# octanis_eps_v05.net
KiCad netlist of a schematic drawn in EAGLE
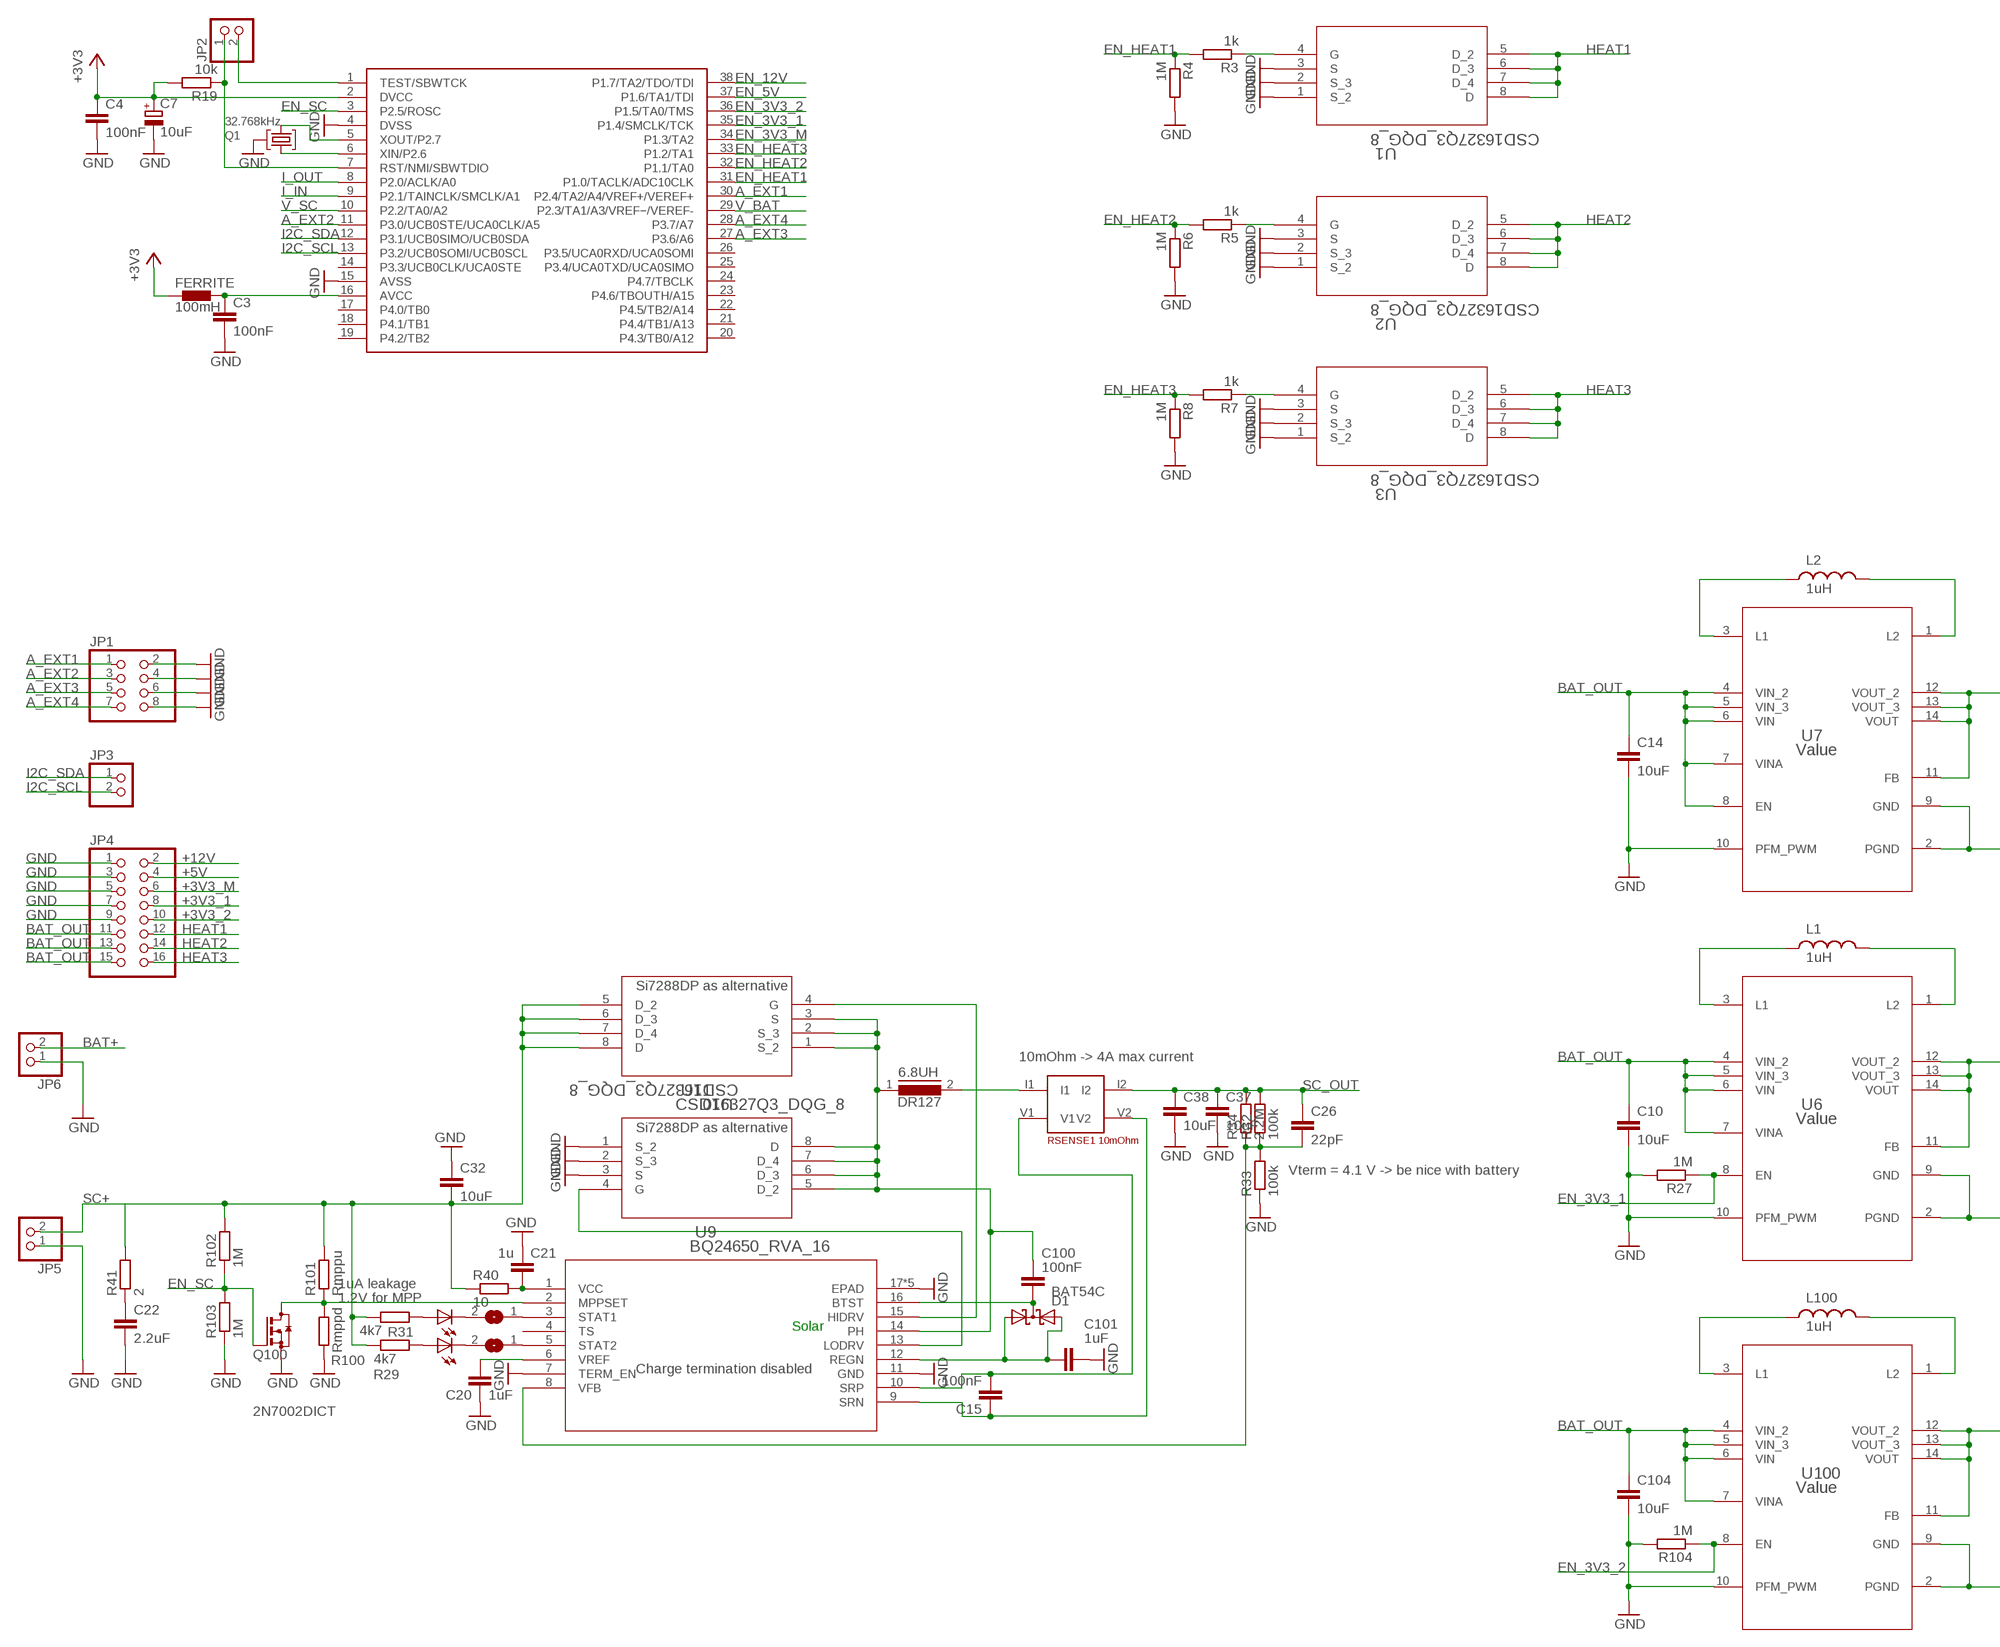
[diagram p0: schematic, sheet 1, part 1 of 2]
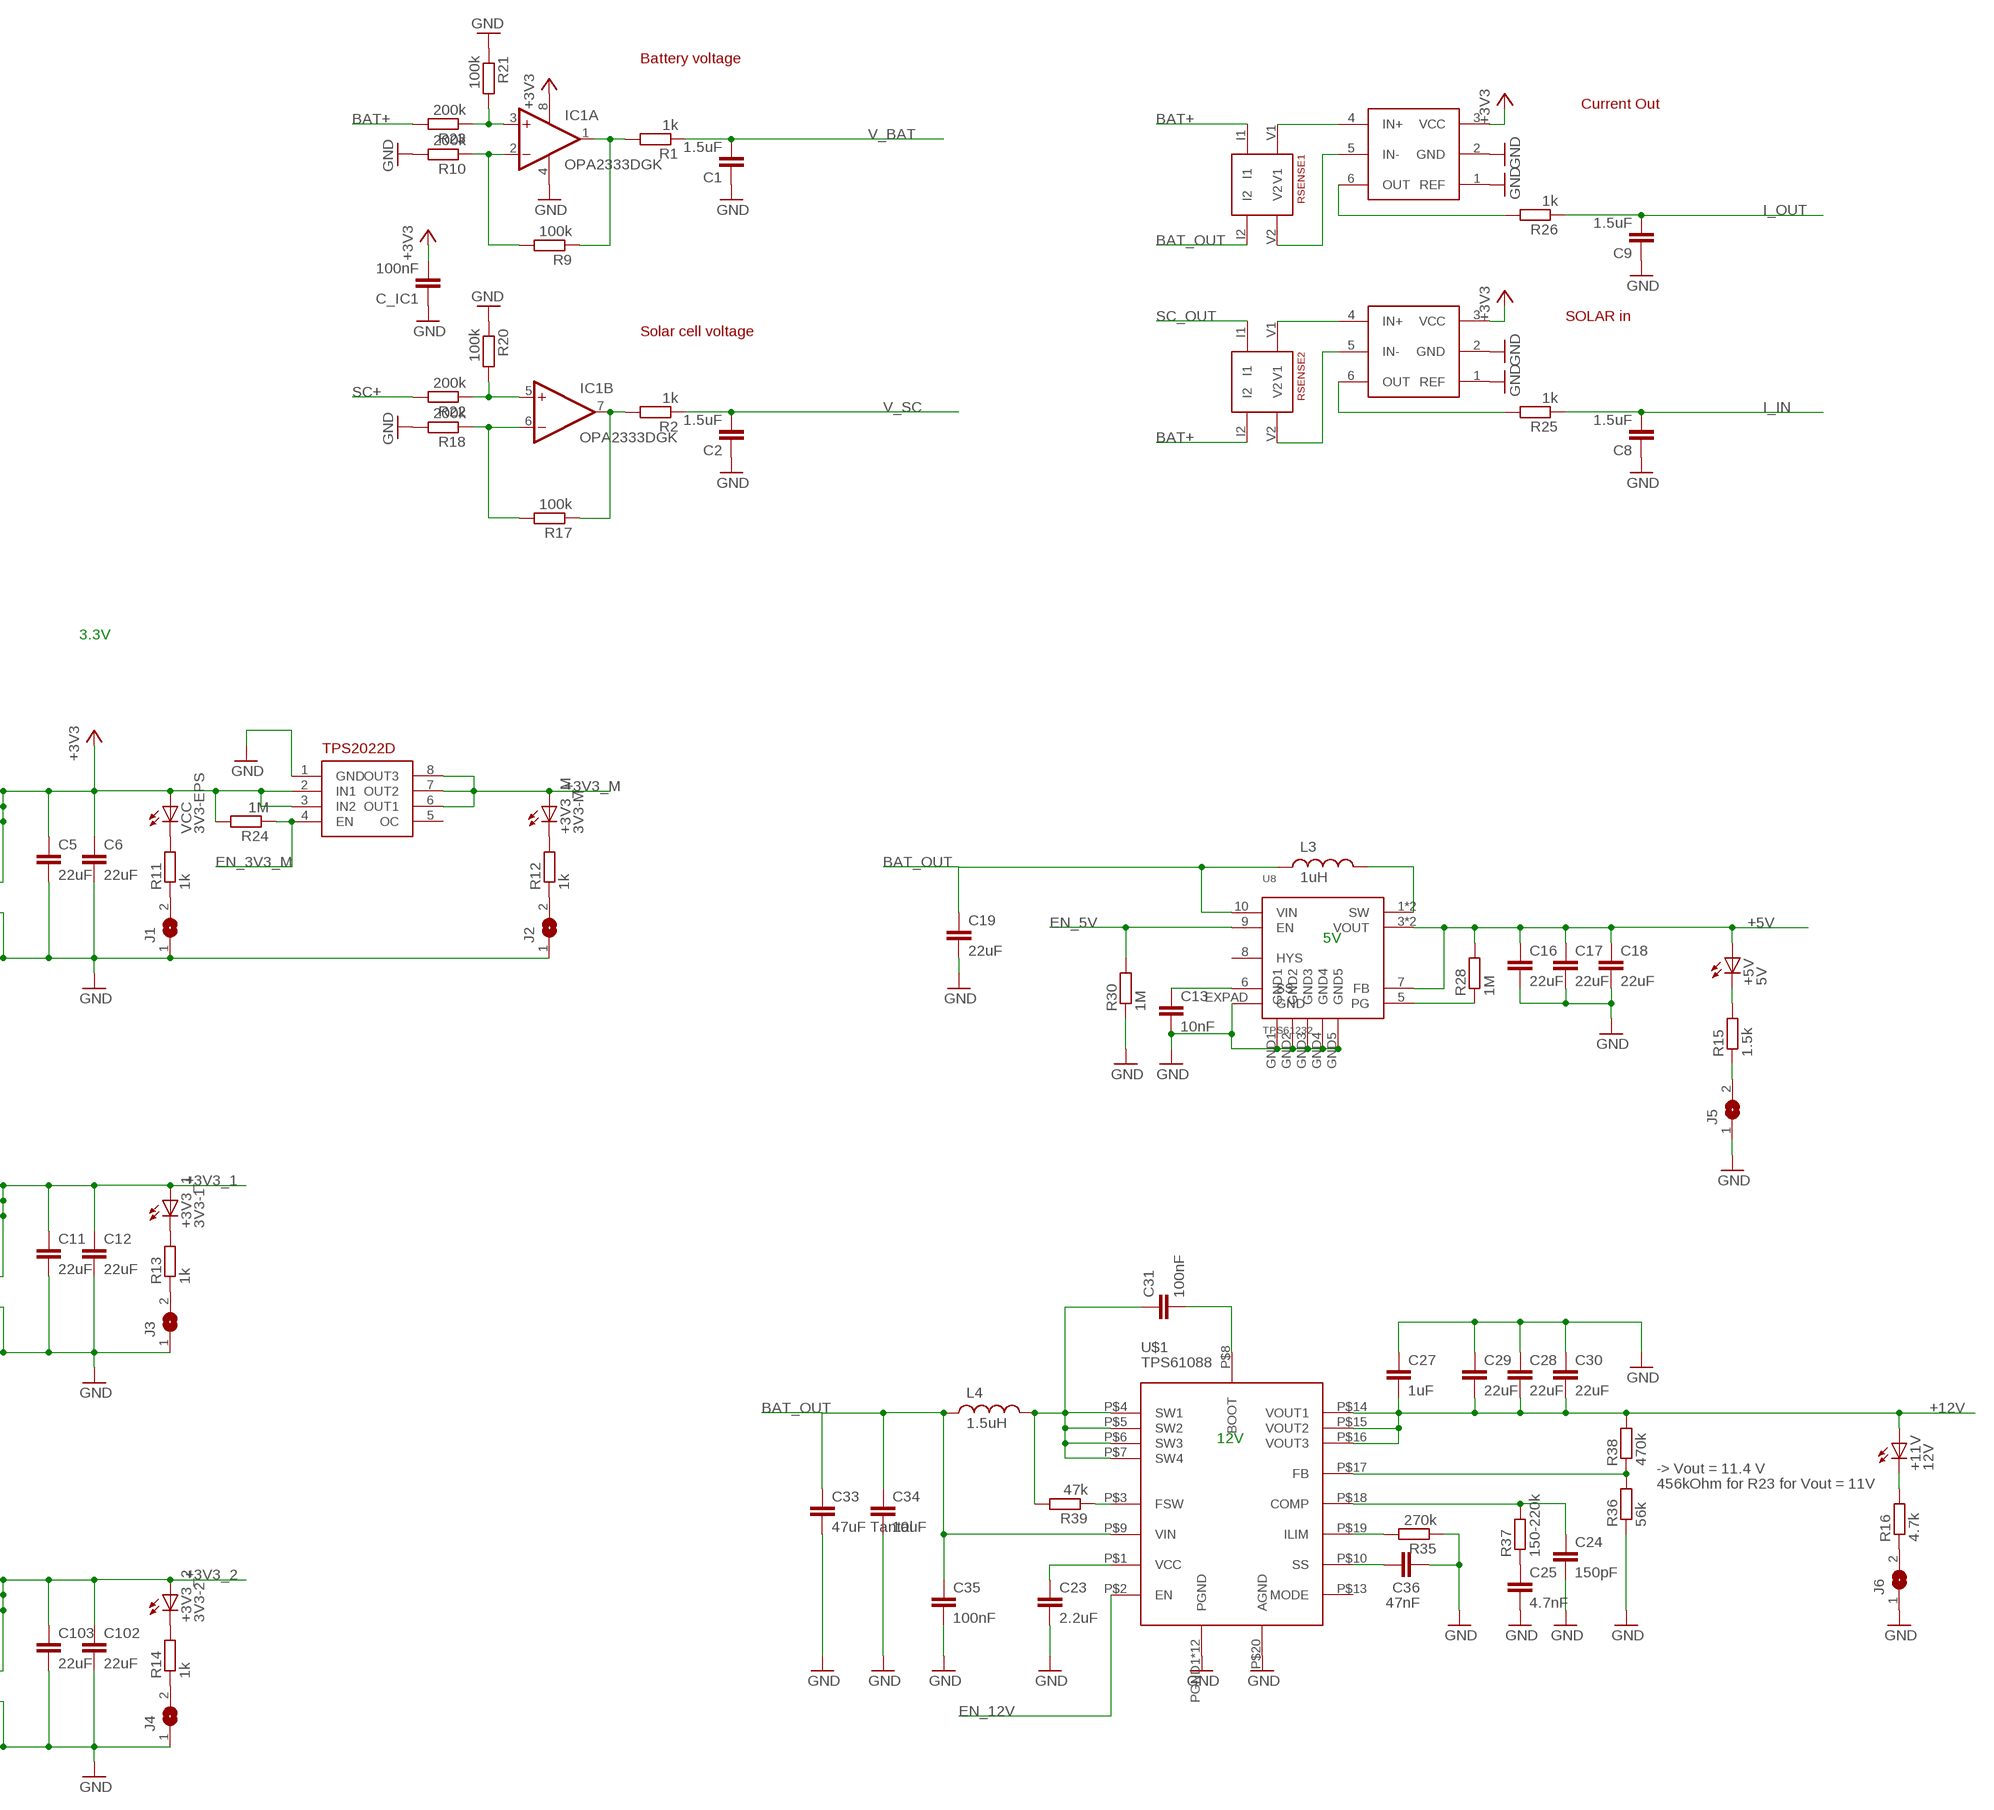
[diagram p1: schematic, sheet 1, part 2 of 2]

(export (version "E")
  (design (tool "Eeschema 10.0.6"))
  (components
    (comp (ref "+3V3_1")
      (value "3V3-1")
      (footprint "eagle-import:CHIPLED_0603")
      (libsource (lib "eagle-import") (part "LEDCHIPLED_0603"))
    )
    (comp (ref "+3V3_2")
      (value "3V3-2")
      (footprint "eagle-import:CHIPLED_0603")
      (libsource (lib "eagle-import") (part "LEDCHIPLED_0603"))
    )
    (comp (ref "+3V3_M")
      (value "3V3-M")
      (footprint "eagle-import:CHIPLED_0603")
      (libsource (lib "eagle-import") (part "LEDCHIPLED_0603"))
    )
    (comp (ref "+5V")
      (value "5V")
      (footprint "eagle-import:CHIPLED_0603")
      (libsource (lib "eagle-import") (part "LEDCHIPLED_0603"))
    )
    (comp (ref "+11V")
      (value "12V")
      (footprint "eagle-import:CHIPLED_0603")
      (libsource (lib "eagle-import") (part "LEDCHIPLED_0603"))
    )
    (comp (ref "6.8UH")
      (value "DR127")
      (footprint "eagle-import:DR127")
      (libsource (lib "eagle-import") (part "DR127"))
    )
    (comp (ref "C1")
      (value "1.5uF")
      (footprint "eagle-import:C0603")
      (libsource (lib "eagle-import") (part "C-EUC0603"))
    )
    (comp (ref "C2")
      (value "1.5uF")
      (footprint "eagle-import:C0603")
      (libsource (lib "eagle-import") (part "C-EUC0603"))
    )
    (comp (ref "C3")
      (value "100nF")
      (footprint "eagle-import:C0603")
      (libsource (lib "eagle-import") (part "C-EUC0603"))
    )
    (comp (ref "C4")
      (value "100nF")
      (footprint "eagle-import:C0603")
      (libsource (lib "eagle-import") (part "C-EUC0603"))
    )
    (comp (ref "C5")
      (value "22uF")
      (footprint "eagle-import:C0805")
      (libsource (lib "eagle-import") (part "resistor_C-EUC0805"))
    )
    (comp (ref "C6")
      (value "22uF")
      (footprint "eagle-import:C0805")
      (libsource (lib "eagle-import") (part "resistor_C-EUC0805"))
    )
    (comp (ref "C7")
      (value "10uF")
      (footprint "eagle-import:A_3216-18R")
      (libsource (lib "eagle-import") (part "CPOL-EUA/3216-18R"))
    )
    (comp (ref "C8")
      (value "1.5uF")
      (footprint "eagle-import:C0603")
      (libsource (lib "eagle-import") (part "C-EUC0603"))
    )
    (comp (ref "C9")
      (value "1.5uF")
      (footprint "eagle-import:C0603")
      (libsource (lib "eagle-import") (part "C-EUC0603"))
    )
    (comp (ref "C10")
      (value "10uF")
      (footprint "eagle-import:C0805")
      (libsource (lib "eagle-import") (part "resistor_C-EUC0805"))
    )
    (comp (ref "C11")
      (value "22uF")
      (footprint "eagle-import:C0805")
      (libsource (lib "eagle-import") (part "resistor_C-EUC0805"))
    )
    (comp (ref "C12")
      (value "22uF")
      (footprint "eagle-import:C0805")
      (libsource (lib "eagle-import") (part "resistor_C-EUC0805"))
    )
    (comp (ref "C13")
      (value "10nF")
      (footprint "eagle-import:C0603")
      (libsource (lib "eagle-import") (part "C-EUC0603"))
    )
    (comp (ref "C14")
      (value "10uF")
      (footprint "eagle-import:C0805")
      (libsource (lib "eagle-import") (part "resistor_C-EUC0805"))
    )
    (comp (ref "C15")
      (value "100nF")
      (footprint "eagle-import:C0603")
      (libsource (lib "eagle-import") (part "C-EUC0603"))
    )
    (comp (ref "C16")
      (value "22uF")
      (footprint "eagle-import:C0805")
      (libsource (lib "eagle-import") (part "resistor_C-EUC0805"))
    )
    (comp (ref "C17")
      (value "22uF")
      (footprint "eagle-import:C0805")
      (libsource (lib "eagle-import") (part "resistor_C-EUC0805"))
    )
    (comp (ref "C18")
      (value "22uF")
      (footprint "eagle-import:C0805")
      (libsource (lib "eagle-import") (part "resistor_C-EUC0805"))
    )
    (comp (ref "C19")
      (value "22uF")
      (footprint "eagle-import:C0603")
      (libsource (lib "eagle-import") (part "C-EUC0603"))
    )
    (comp (ref "C20")
      (value "1uF")
      (footprint "eagle-import:C0603")
      (libsource (lib "eagle-import") (part "C-EUC0603"))
    )
    (comp (ref "C21")
      (value "1u")
      (footprint "eagle-import:C0603")
      (libsource (lib "eagle-import") (part "C-EUC0603"))
    )
    (comp (ref "C22")
      (value "2.2uF")
      (footprint "eagle-import:C0603")
      (libsource (lib "eagle-import") (part "C-EUC0603"))
    )
    (comp (ref "C23")
      (value "2.2uF")
      (footprint "eagle-import:C0603")
      (libsource (lib "eagle-import") (part "C-EUC0603"))
    )
    (comp (ref "C24")
      (value "150pF")
      (footprint "eagle-import:C0603")
      (libsource (lib "eagle-import") (part "C-EUC0603"))
    )
    (comp (ref "C25")
      (value "4.7nF")
      (footprint "eagle-import:C0603")
      (libsource (lib "eagle-import") (part "C-EUC0603"))
    )
    (comp (ref "C26")
      (value "22pF")
      (footprint "eagle-import:C0603")
      (libsource (lib "eagle-import") (part "C-EUC0603"))
    )
    (comp (ref "C27")
      (value "1uF")
      (footprint "eagle-import:C0603")
      (libsource (lib "eagle-import") (part "C-EUC0603"))
    )
    (comp (ref "C28")
      (value "22uF")
      (footprint "eagle-import:C0805")
      (libsource (lib "eagle-import") (part "resistor_C-EUC0805"))
    )
    (comp (ref "C29")
      (value "22uF")
      (footprint "eagle-import:C0805")
      (libsource (lib "eagle-import") (part "resistor_C-EUC0805"))
    )
    (comp (ref "C30")
      (value "22uF")
      (footprint "eagle-import:C0805")
      (libsource (lib "eagle-import") (part "resistor_C-EUC0805"))
    )
    (comp (ref "C31")
      (value "100nF")
      (footprint "eagle-import:C0603")
      (libsource (lib "eagle-import") (part "C-EUC0603"))
    )
    (comp (ref "C32")
      (value "10uF")
      (footprint "eagle-import:C0805")
      (libsource (lib "eagle-import") (part "resistor_C-EUC0805"))
    )
    (comp (ref "C33")
      (value "47uF Tantal")
      (footprint "eagle-import:C1210")
      (libsource (lib "eagle-import") (part "C-EUC1210"))
    )
    (comp (ref "C34")
      (value "10uF")
      (footprint "eagle-import:C0805")
      (libsource (lib "eagle-import") (part "resistor_C-EUC0805"))
    )
    (comp (ref "C35")
      (value "100nF")
      (footprint "eagle-import:C0603")
      (libsource (lib "eagle-import") (part "C-EUC0603"))
    )
    (comp (ref "C36")
      (value "47nF")
      (footprint "eagle-import:C0603")
      (libsource (lib "eagle-import") (part "C-EUC0603"))
    )
    (comp (ref "C37")
      (value "10uF")
      (footprint "eagle-import:C0805")
      (libsource (lib "eagle-import") (part "resistor_C-EUC0805"))
    )
    (comp (ref "C38")
      (value "10uF")
      (footprint "eagle-import:C0805")
      (libsource (lib "eagle-import") (part "resistor_C-EUC0805"))
    )
    (comp (ref "C100")
      (value "100nF")
      (footprint "eagle-import:C0603")
      (libsource (lib "eagle-import") (part "C-EUC0603"))
    )
    (comp (ref "C101")
      (value "1uF")
      (footprint "eagle-import:C0603")
      (libsource (lib "eagle-import") (part "C-EUC0603"))
    )
    (comp (ref "C102")
      (value "22uF")
      (footprint "eagle-import:C0805")
      (libsource (lib "eagle-import") (part "resistor_C-EUC0805"))
    )
    (comp (ref "C103")
      (value "22uF")
      (footprint "eagle-import:C0805")
      (libsource (lib "eagle-import") (part "resistor_C-EUC0805"))
    )
    (comp (ref "C104")
      (value "10uF")
      (footprint "eagle-import:C0805")
      (libsource (lib "eagle-import") (part "resistor_C-EUC0805"))
    )
    (comp (ref "C_IC1")
      (value "100nF")
      (footprint "eagle-import:C0603")
      (libsource (lib "eagle-import") (part "C-EUC0603"))
    )
    (comp (ref "D1")
      (value "BAT54C")
      (footprint "eagle-import:SOT23")
      (libsource (lib "eagle-import") (part "BAT54C"))
    )
    (comp (ref "FERRITE")
      (value "100mH")
      (footprint "eagle-import:0402")
      (libsource (lib "eagle-import") (part "BLM15HD601SN1"))
    )
    (comp (ref "IC1")
      (value "OPA2333DGK")
      (footprint "eagle-import:MSOP08")
      (libsource (lib "eagle-import") (part "OPA2333DGK"))
    )
    (comp (ref "J1") (value "SJ") (footprint "eagle-import:SJ") (libsource (lib "eagle-import") (part "SJ")))
    (comp (ref "J2") (value "SJ") (footprint "eagle-import:SJ") (libsource (lib "eagle-import") (part "SJ")))
    (comp (ref "J3") (value "SJ") (footprint "eagle-import:SJ") (libsource (lib "eagle-import") (part "SJ")))
    (comp (ref "J4") (value "SJ") (footprint "eagle-import:SJ") (libsource (lib "eagle-import") (part "SJ")))
    (comp (ref "J5") (value "SJ") (footprint "eagle-import:SJ") (libsource (lib "eagle-import") (part "SJ")))
    (comp (ref "J6") (value "SJ") (footprint "eagle-import:SJ") (libsource (lib "eagle-import") (part "SJ")))
    (comp (ref "J7") (value "SJ") (footprint "eagle-import:SJ") (libsource (lib "eagle-import") (part "SJ")))
    (comp (ref "J8") (value "SJ") (footprint "eagle-import:SJ") (libsource (lib "eagle-import") (part "SJ")))
    (comp (ref "JP1")
      (value "PINHD-2X4")
      (footprint "eagle-import:2X04")
      (libsource (lib "eagle-import") (part "PINHD-2X4"))
    )
    (comp (ref "JP2")
      (value "PINHD-1X2")
      (footprint "eagle-import:1X02")
      (libsource (lib "eagle-import") (part "PINHD-1X2"))
    )
    (comp (ref "JP3")
      (value "PINHD-1X2")
      (footprint "eagle-import:1X02")
      (libsource (lib "eagle-import") (part "PINHD-1X2"))
    )
    (comp (ref "JP4")
      (value "PINHD-2X8")
      (footprint "eagle-import:2X08")
      (libsource (lib "eagle-import") (part "PINHD-2X8"))
    )
    (comp (ref "JP5")
      (value "PINHD-1X2")
      (footprint "eagle-import:1X02")
      (libsource (lib "eagle-import") (part "PINHD-1X2"))
    )
    (comp (ref "JP6")
      (value "PINHD-1X2")
      (footprint "eagle-import:1X02")
      (libsource (lib "eagle-import") (part "PINHD-1X2"))
    )
    (comp (ref "L1")
      (value "1uH")
      (footprint "eagle-import:XFL4020")
      (libsource (lib "eagle-import") (part "XFL4020"))
    )
    (comp (ref "L2")
      (value "1uH")
      (footprint "eagle-import:XFL4020")
      (libsource (lib "eagle-import") (part "XFL4020"))
    )
    (comp (ref "L3")
      (value "1uH")
      (footprint "eagle-import:XFL4020")
      (libsource (lib "eagle-import") (part "XFL4020"))
    )
    (comp (ref "L4")
      (value "1.5uH")
      (footprint "eagle-import:XFL4020")
      (libsource (lib "eagle-import") (part "XFL4020"))
    )
    (comp (ref "L100")
      (value "1uH")
      (footprint "eagle-import:XFL4020")
      (libsource (lib "eagle-import") (part "XFL4020"))
    )
    (comp (ref "Q1")
      (value "32.768kHz")
      (footprint "eagle-import:MS3V-T1R")
      (libsource (lib "eagle-import") (part "MS3V-T1R"))
    )
    (comp (ref "Q100")
      (value "BSS123")
      (footprint "eagle-import:SOT23")
      (libsource (lib "eagle-import") (part "BSS123"))
    )
    (comp (ref "R1")
      (value "1k")
      (footprint "eagle-import:R0603")
      (libsource (lib "eagle-import") (part "R-EU_R0603"))
    )
    (comp (ref "R2")
      (value "1k")
      (footprint "eagle-import:R0603")
      (libsource (lib "eagle-import") (part "R-EU_R0603"))
    )
    (comp (ref "R3")
      (value "1k")
      (footprint "eagle-import:R0603")
      (libsource (lib "eagle-import") (part "R-EU_R0603"))
    )
    (comp (ref "R4")
      (value "1M")
      (footprint "eagle-import:R0603")
      (libsource (lib "eagle-import") (part "R-EU_R0603"))
    )
    (comp (ref "R5")
      (value "1k")
      (footprint "eagle-import:R0603")
      (libsource (lib "eagle-import") (part "R-EU_R0603"))
    )
    (comp (ref "R6")
      (value "1M")
      (footprint "eagle-import:R0603")
      (libsource (lib "eagle-import") (part "R-EU_R0603"))
    )
    (comp (ref "R7")
      (value "1k")
      (footprint "eagle-import:R0603")
      (libsource (lib "eagle-import") (part "R-EU_R0603"))
    )
    (comp (ref "R8")
      (value "1M")
      (footprint "eagle-import:R0603")
      (libsource (lib "eagle-import") (part "R-EU_R0603"))
    )
    (comp (ref "R9")
      (value "100k")
      (footprint "eagle-import:R0603")
      (libsource (lib "eagle-import") (part "R-EU_R0603"))
    )
    (comp (ref "R10")
      (value "200k")
      (footprint "eagle-import:R0603")
      (libsource (lib "eagle-import") (part "R-EU_R0603"))
    )
    (comp (ref "R11")
      (value "1k")
      (footprint "eagle-import:R0603")
      (libsource (lib "eagle-import") (part "R-EU_R0603"))
    )
    (comp (ref "R12")
      (value "1k")
      (footprint "eagle-import:R0603")
      (libsource (lib "eagle-import") (part "R-EU_R0603"))
    )
    (comp (ref "R13")
      (value "1k")
      (footprint "eagle-import:R0603")
      (libsource (lib "eagle-import") (part "R-EU_R0603"))
    )
    (comp (ref "R14")
      (value "1k")
      (footprint "eagle-import:R0603")
      (libsource (lib "eagle-import") (part "R-EU_R0603"))
    )
    (comp (ref "R15")
      (value "1.5k")
      (footprint "eagle-import:R0603")
      (libsource (lib "eagle-import") (part "R-EU_R0603"))
    )
    (comp (ref "R16")
      (value "4.7k")
      (footprint "eagle-import:R0603")
      (libsource (lib "eagle-import") (part "R-EU_R0603"))
    )
    (comp (ref "R17")
      (value "100k")
      (footprint "eagle-import:R0603")
      (libsource (lib "eagle-import") (part "R-EU_R0603"))
    )
    (comp (ref "R18")
      (value "200k")
      (footprint "eagle-import:R0603")
      (libsource (lib "eagle-import") (part "R-EU_R0603"))
    )
    (comp (ref "R19")
      (value "10k")
      (footprint "eagle-import:R0603")
      (libsource (lib "eagle-import") (part "R-EU_R0603"))
    )
    (comp (ref "R20")
      (value "100k")
      (footprint "eagle-import:R0603")
      (libsource (lib "eagle-import") (part "R-EU_R0603"))
    )
    (comp (ref "R21")
      (value "100k")
      (footprint "eagle-import:R0603")
      (libsource (lib "eagle-import") (part "R-EU_R0603"))
    )
    (comp (ref "R22")
      (value "200k")
      (footprint "eagle-import:R0603")
      (libsource (lib "eagle-import") (part "R-EU_R0603"))
    )
    (comp (ref "R23")
      (value "200k")
      (footprint "eagle-import:R0603")
      (libsource (lib "eagle-import") (part "R-EU_R0603"))
    )
    (comp (ref "R24")
      (value "1M")
      (footprint "eagle-import:R0603")
      (libsource (lib "eagle-import") (part "resistor_R-EU_R0603"))
    )
    (comp (ref "R25")
      (value "1k")
      (footprint "eagle-import:R0603")
      (libsource (lib "eagle-import") (part "R-EU_R0603"))
    )
    (comp (ref "R26")
      (value "1k")
      (footprint "eagle-import:R0603")
      (libsource (lib "eagle-import") (part "R-EU_R0603"))
    )
    (comp (ref "R27")
      (value "1M")
      (footprint "eagle-import:R0603")
      (libsource (lib "eagle-import") (part "resistor_R-EU_R0603"))
    )
    (comp (ref "R28")
      (value "1M")
      (footprint "eagle-import:R0603")
      (libsource (lib "eagle-import") (part "R-EU_R0603"))
    )
    (comp (ref "R29")
      (value "4k7")
      (footprint "eagle-import:R0603")
      (libsource (lib "eagle-import") (part "R-EU_R0603"))
    )
    (comp (ref "R30")
      (value "1M")
      (footprint "eagle-import:R0603")
      (libsource (lib "eagle-import") (part "R-EU_R0603"))
    )
    (comp (ref "R31")
      (value "4k7")
      (footprint "eagle-import:R0603")
      (libsource (lib "eagle-import") (part "R-EU_R0603"))
    )
    (comp (ref "R32")
      (value "100k")
      (footprint "eagle-import:R0603")
      (libsource (lib "eagle-import") (part "R-EU_R0603"))
    )
    (comp (ref "R33")
      (value "100k")
      (footprint "eagle-import:R0603")
      (libsource (lib "eagle-import") (part "R-EU_R0603"))
    )
    (comp (ref "R34")
      (value "2.2M")
      (footprint "eagle-import:R0603")
      (libsource (lib "eagle-import") (part "R-EU_R0603"))
    )
    (comp (ref "R35")
      (value "270k")
      (footprint "eagle-import:R0603")
      (libsource (lib "eagle-import") (part "resistor_R-EU_R0603"))
    )
    (comp (ref "R36")
      (value "56k")
      (footprint "eagle-import:R0603")
      (libsource (lib "eagle-import") (part "resistor_R-EU_R0603"))
    )
    (comp (ref "R37")
      (value "150-220k")
      (footprint "eagle-import:R0603")
      (libsource (lib "eagle-import") (part "resistor_R-EU_R0603"))
    )
    (comp (ref "R38")
      (value "470k")
      (footprint "eagle-import:R0603")
      (libsource (lib "eagle-import") (part "resistor_R-EU_R0603"))
    )
    (comp (ref "R39")
      (value "47k")
      (footprint "eagle-import:R0603")
      (libsource (lib "eagle-import") (part "resistor_R-EU_R0603"))
    )
    (comp (ref "R40")
      (value "10")
      (footprint "eagle-import:R1206")
      (libsource (lib "eagle-import") (part "R-EU_R1206"))
    )
    (comp (ref "R41")
      (value "2")
      (footprint "eagle-import:R2012")
      (libsource (lib "eagle-import") (part "R-EU_R2012"))
    )
    (comp (ref "R100")
      (value "Rmppd")
      (footprint "eagle-import:R0603")
      (libsource (lib "eagle-import") (part "R-EU_R0603"))
    )
    (comp (ref "R101")
      (value "Rmppu")
      (footprint "eagle-import:R0603")
      (libsource (lib "eagle-import") (part "R-EU_R0603"))
    )
    (comp (ref "R102")
      (value "1M")
      (footprint "eagle-import:R0603")
      (libsource (lib "eagle-import") (part "R-EU_R0603"))
    )
    (comp (ref "R103")
      (value "1M")
      (footprint "eagle-import:R0603")
      (libsource (lib "eagle-import") (part "R-EU_R0603"))
    )
    (comp (ref "R104")
      (value "1M")
      (footprint "eagle-import:R0603")
      (libsource (lib "eagle-import") (part "resistor_R-EU_R0603"))
    )
    (comp (ref "RSENSE1")
      (value "RSENSE2")
      (footprint "eagle-import:4PADS_RESISTOR")
      (libsource (lib "eagle-import") (part "CURRENT_RESISTOR"))
    )
    (comp (ref "R_SENSE1")
      (value "RSENSE1 10mOhm")
      (footprint "eagle-import:4PADS_RESISTOR")
      (libsource (lib "eagle-import") (part "CURRENT_RESISTOR"))
    )
    (comp (ref "R_SENSE2")
      (value "RSENSE1")
      (footprint "eagle-import:4PADS_RESISTOR")
      (libsource (lib "eagle-import") (part "CURRENT_RESISTOR"))
    )
    (comp (ref "STAT1")
      (value "5V-ok")
      (footprint "eagle-import:CHIPLED_0603")
      (libsource (lib "eagle-import") (part "LEDCHIPLED_0603"))
    )
    (comp (ref "STAT2")
      (value "5V-ok")
      (footprint "eagle-import:CHIPLED_0603")
      (libsource (lib "eagle-import") (part "LEDCHIPLED_0603"))
    )
    (comp (ref "U$1")
      (value "TPS61088")
      (footprint "eagle-import:R-PVQFN-N20")
      (libsource (lib "eagle-import") (part "TPS61088"))
    )
    (comp (ref "U$2")
      (value "INA213")
      (footprint "eagle-import:SC70-6")
      (libsource (lib "eagle-import") (part "INA213"))
    )
    (comp (ref "U$3")
      (value "INA213")
      (footprint "eagle-import:SC70-6")
      (libsource (lib "eagle-import") (part "INA213"))
    )
    (comp (ref "U1")
      (value "CSD16327Q3_DQG_8")
      (footprint "eagle-import:DQG8")
      (fields
        (field (name "GENERIC_PART_NUMBER") "CSD16327Q3")
        (field (name "MANUFACTURER") "Texas Instruments")
      )
      (libsource (lib "eagle-import") (part "CSD16327Q3_DQG_8"))
    )
    (comp (ref "U2")
      (value "CSD16327Q3_DQG_8")
      (footprint "eagle-import:DQG8")
      (fields
        (field (name "GENERIC_PART_NUMBER") "CSD16327Q3")
        (field (name "MANUFACTURER") "Texas Instruments")
      )
      (libsource (lib "eagle-import") (part "CSD16327Q3_DQG_8"))
    )
    (comp (ref "U3")
      (value "CSD16327Q3_DQG_8")
      (footprint "eagle-import:DQG8")
      (fields
        (field (name "GENERIC_PART_NUMBER") "CSD16327Q3")
        (field (name "MANUFACTURER") "Texas Instruments")
      )
      (libsource (lib "eagle-import") (part "CSD16327Q3_DQG_8"))
    )
    (comp (ref "U4")
      (value "MSP430G2544")
      (footprint "eagle-import:TSSOP38")
      (libsource (lib "eagle-import") (part "MSP430G2544"))
    )
    (comp (ref "U5")
      (value "TPS2022D")
      (footprint "eagle-import:SO8")
      (libsource (lib "eagle-import") (part "TPS2022D"))
    )
    (comp (ref "U6")
      (value "Value")
      (footprint "eagle-import:RNC0014A")
      (fields
        (field (name "ALTERNATEPARTNUMBER") "TPS630250RNCT")
        (field (name "MANUFACTURER") "Texas Instruments")
        (field (name "PARTNUMBER") "TPS630250RNCR")
      )
      (libsource (lib "eagle-import") (part "TPS630250RNCR"))
    )
    (comp (ref "U7")
      (value "Value")
      (footprint "eagle-import:RNC0014A")
      (fields
        (field (name "ALTERNATEPARTNUMBER") "TPS630250RNCT")
        (field (name "MANUFACTURER") "Texas Instruments")
        (field (name "PARTNUMBER") "TPS630250RNCR")
      )
      (libsource (lib "eagle-import") (part "TPS630250RNCR"))
    )
    (comp (ref "U8")
      (value "TPS61232")
      (footprint "eagle-import:S-PVSON-N10")
      (libsource (lib "eagle-import") (part "TPS61232"))
    )
    (comp (ref "U9")
      (value "BQ24650_RVA_16")
      (footprint "eagle-import:RVA16_2P14X2P14")
      (fields
        (field (name "GENERIC_PART_NUMBER") "BQ24650")
        (field (name "MANUFACTURER") "Texas Instruments")
      )
      (libsource (lib "eagle-import") (part "BQ24650_RVA_16"))
    )
    (comp (ref "U10")
      (value "CSD16327Q3_DQG_8")
      (footprint "eagle-import:DQG8")
      (fields
        (field (name "GENERIC_PART_NUMBER") "CSD16327Q3")
        (field (name "MANUFACTURER") "Texas Instruments")
      )
      (libsource (lib "eagle-import") (part "CSD16327Q3_DQG_8"))
    )
    (comp (ref "U11")
      (value "CSD16327Q3_DQG_8")
      (footprint "eagle-import:DQG8")
      (fields
        (field (name "GENERIC_PART_NUMBER") "CSD16327Q3")
        (field (name "MANUFACTURER") "Texas Instruments")
      )
      (libsource (lib "eagle-import") (part "CSD16327Q3_DQG_8"))
    )
    (comp (ref "U100")
      (value "Value")
      (footprint "eagle-import:RNC0014A")
      (fields
        (field (name "ALTERNATEPARTNUMBER") "TPS630250RNCT")
        (field (name "MANUFACTURER") "Texas Instruments")
        (field (name "PARTNUMBER") "TPS630250RNCR")
      )
      (libsource (lib "eagle-import") (part "TPS630250RNCR"))
    )
    (comp (ref "VCC")
      (value "3V3-EPS")
      (footprint "eagle-import:CHIPLED_0603")
      (libsource (lib "eagle-import") (part "LEDCHIPLED_0603"))
    )
  )
  (nets
    (net (code "1") (name "+3V3") (class "Default")
      (node (ref "C4") (pin "1") (pinfunction "1_1") (pintype "passive"))
      (node (ref "C5") (pin "1") (pinfunction "1_1") (pintype "passive"))
      (node (ref "C6") (pin "1") (pinfunction "1_1") (pintype "passive"))
      (node (ref "C7") (pin "+") (pinfunction "+_+") (pintype "passive"))
      (node (ref "C_IC1") (pin "2") (pinfunction "2_2") (pintype "passive"))
      (node (ref "FERRITE") (pin "1") (pinfunction "1_1") (pintype "passive"))
      (node (ref "IC1") (pin "8") (pinfunction "V+_8") (pintype "power_in"))
      (node (ref "R19") (pin "2") (pinfunction "2_2") (pintype "passive"))
      (node (ref "R24") (pin "2") (pinfunction "2_2") (pintype "passive"))
      (node (ref "U$2") (pin "3") (pinfunction "VCC_3") (pintype "bidirectional"))
      (node (ref "U$3") (pin "3") (pinfunction "VCC_3") (pintype "bidirectional"))
      (node (ref "U4") (pin "2") (pinfunction "DVCC_2") (pintype "bidirectional"))
      (node (ref "U5") (pin "2") (pinfunction "IN1_2") (pintype "bidirectional"))
      (node (ref "U5") (pin "3") (pinfunction "IN2_3") (pintype "bidirectional"))
      (node (ref "U7") (pin "11") (pinfunction "FB_11") (pintype "input"))
      (node (ref "U7") (pin "12") (pinfunction "VOUT_2_12") (pintype "power_in"))
      (node (ref "U7") (pin "13") (pinfunction "VOUT_3_13") (pintype "power_in"))
      (node (ref "U7") (pin "14") (pinfunction "VOUT_14") (pintype "power_in"))
      (node (ref "VCC") (pin "A") (pinfunction "A_A") (pintype "passive"))
    )
    (net (code "2") (name "/+3V3_1") (class "Default")
      (node (ref "+3V3_1") (pin "A") (pinfunction "A_A") (pintype "passive"))
      (node (ref "C11") (pin "1") (pinfunction "1_1") (pintype "passive"))
      (node (ref "C12") (pin "1") (pinfunction "1_1") (pintype "passive"))
      (node (ref "JP4") (pin "8") (pinfunction "8_8") (pintype "passive"))
      (node (ref "U6") (pin "11") (pinfunction "FB_11") (pintype "input"))
      (node (ref "U6") (pin "12") (pinfunction "VOUT_2_12") (pintype "power_in"))
      (node (ref "U6") (pin "13") (pinfunction "VOUT_3_13") (pintype "power_in"))
      (node (ref "U6") (pin "14") (pinfunction "VOUT_14") (pintype "power_in"))
    )
    (net (code "3") (name "/+3V3_2") (class "Default")
      (node (ref "+3V3_2") (pin "A") (pinfunction "A_A") (pintype "passive"))
      (node (ref "C102") (pin "1") (pinfunction "1_1") (pintype "passive"))
      (node (ref "C103") (pin "1") (pinfunction "1_1") (pintype "passive"))
      (node (ref "JP4") (pin "10") (pinfunction "10_10") (pintype "passive"))
      (node (ref "U100") (pin "11") (pinfunction "FB_11") (pintype "input"))
      (node (ref "U100") (pin "12") (pinfunction "VOUT_2_12") (pintype "power_in"))
      (node (ref "U100") (pin "13") (pinfunction "VOUT_3_13") (pintype "power_in"))
      (node (ref "U100") (pin "14") (pinfunction "VOUT_14") (pintype "power_in"))
    )
    (net (code "4") (name "/+3V3_M") (class "Default")
      (node (ref "+3V3_M") (pin "A") (pinfunction "A_A") (pintype "passive"))
      (node (ref "JP4") (pin "6") (pinfunction "6_6") (pintype "passive"))
      (node (ref "U5") (pin "6") (pinfunction "OUT1_6") (pintype "bidirectional"))
      (node (ref "U5") (pin "7") (pinfunction "OUT2_7") (pintype "bidirectional"))
      (node (ref "U5") (pin "8") (pinfunction "OUT3_8") (pintype "bidirectional"))
    )
    (net (code "5") (name "/+5V") (class "Default")
      (node (ref "+5V") (pin "A") (pinfunction "A_A") (pintype "passive"))
      (node (ref "C16") (pin "1") (pinfunction "1_1") (pintype "passive"))
      (node (ref "C17") (pin "1") (pinfunction "1_1") (pintype "passive"))
      (node (ref "C18") (pin "1") (pinfunction "1_1") (pintype "passive"))
      (node (ref "JP4") (pin "4") (pinfunction "4_4") (pintype "passive"))
      (node (ref "R28") (pin "2") (pinfunction "2_2") (pintype "passive"))
      (node (ref "U8") (pin "3") (pinfunction "VOUT_3") (pintype "power_in"))
      (node (ref "U8") (pin "4") (pinfunction "VOUT_4") (pintype "power_in"))
      (node (ref "U8") (pin "7") (pinfunction "FB_7") (pintype "input"))
    )
    (net (code "6") (name "/+12V") (class "Default")
      (node (ref "+11V") (pin "A") (pinfunction "A_A") (pintype "passive"))
      (node (ref "C27") (pin "2") (pinfunction "2_2") (pintype "passive"))
      (node (ref "C28") (pin "2") (pinfunction "2_2") (pintype "passive"))
      (node (ref "C29") (pin "2") (pinfunction "2_2") (pintype "passive"))
      (node (ref "C30") (pin "2") (pinfunction "2_2") (pintype "passive"))
      (node (ref "JP4") (pin "2") (pinfunction "2_2") (pintype "passive"))
      (node (ref "R38") (pin "2") (pinfunction "2_2") (pintype "passive"))
      (node (ref "U$1") (pin "P$14") (pinfunction "VOUT1_P$14") (pintype "bidirectional"))
      (node (ref "U$1") (pin "P$15") (pinfunction "VOUT2_P$15") (pintype "bidirectional"))
      (node (ref "U$1") (pin "P$16") (pinfunction "VOUT3_P$16") (pintype "bidirectional"))
    )
    (net (code "7") (name "/A_EXT1") (class "Default")
      (node (ref "JP1") (pin "1") (pinfunction "1_1") (pintype "passive"))
      (node (ref "U4") (pin "30") (pinfunction "P2.4/TA2/A4/VREF+/VEREF+_30") (pintype "bidirectional"))
    )
    (net (code "8") (name "/A_EXT2") (class "Default")
      (node (ref "JP1") (pin "3") (pinfunction "3_3") (pintype "passive"))
      (node (ref "U4") (pin "11") (pinfunction "P3.0/UCB0STE/UCA0CLK/A5_11") (pintype "bidirectional"))
    )
    (net (code "9") (name "/A_EXT3") (class "Default")
      (node (ref "JP1") (pin "5") (pinfunction "5_5") (pintype "passive"))
      (node (ref "U4") (pin "27") (pinfunction "P3.6/A6_27") (pintype "bidirectional"))
    )
    (net (code "10") (name "/A_EXT4") (class "Default")
      (node (ref "JP1") (pin "7") (pinfunction "7_7") (pintype "passive"))
      (node (ref "U4") (pin "28") (pinfunction "P3.7/A7_28") (pintype "bidirectional"))
    )
    (net (code "11") (name "/BAT+") (class "Default")
      (node (ref "JP6") (pin "2") (pinfunction "2_2") (pintype "passive"))
      (node (ref "R23") (pin "2") (pinfunction "2_2") (pintype "passive"))
      (node (ref "RSENSE1") (pin "I2") (pinfunction "I2_I2") (pintype "bidirectional"))
      (node (ref "R_SENSE2") (pin "I1") (pinfunction "I1_I1") (pintype "bidirectional"))
    )
    (net (code "12") (name "/BAT_OUT") (class "Default")
      (node (ref "C10") (pin "1") (pinfunction "1_1") (pintype "passive"))
      (node (ref "C104") (pin "1") (pinfunction "1_1") (pintype "passive"))
      (node (ref "C14") (pin "1") (pinfunction "1_1") (pintype "passive"))
      (node (ref "C19") (pin "1") (pinfunction "1_1") (pintype "passive"))
      (node (ref "C33") (pin "1") (pinfunction "1_1") (pintype "passive"))
      (node (ref "C34") (pin "1") (pinfunction "1_1") (pintype "passive"))
      (node (ref "C35") (pin "1") (pinfunction "1_1") (pintype "passive"))
      (node (ref "JP4") (pin "11") (pinfunction "11_11") (pintype "passive"))
      (node (ref "JP4") (pin "13") (pinfunction "13_13") (pintype "passive"))
      (node (ref "JP4") (pin "15") (pinfunction "15_15") (pintype "passive"))
      (node (ref "L3") (pin "P$1") (pinfunction "1_P$1") (pintype "passive"))
      (node (ref "L4") (pin "P$1") (pinfunction "1_P$1") (pintype "passive"))
      (node (ref "R_SENSE2") (pin "I2") (pinfunction "I2_I2") (pintype "bidirectional"))
      (node (ref "U$1") (pin "P$9") (pinfunction "VIN_P$9") (pintype "bidirectional"))
      (node (ref "U100") (pin "4") (pinfunction "VIN_2_4") (pintype "power_in"))
      (node (ref "U100") (pin "5") (pinfunction "VIN_3_5") (pintype "power_in"))
      (node (ref "U100") (pin "6") (pinfunction "VIN_6") (pintype "power_in"))
      (node (ref "U100") (pin "7") (pinfunction "VINA_7") (pintype "power_in"))
      (node (ref "U6") (pin "4") (pinfunction "VIN_2_4") (pintype "power_in"))
      (node (ref "U6") (pin "5") (pinfunction "VIN_3_5") (pintype "power_in"))
      (node (ref "U6") (pin "6") (pinfunction "VIN_6") (pintype "power_in"))
      (node (ref "U6") (pin "7") (pinfunction "VINA_7") (pintype "power_in"))
      (node (ref "U7") (pin "4") (pinfunction "VIN_2_4") (pintype "power_in"))
      (node (ref "U7") (pin "5") (pinfunction "VIN_3_5") (pintype "power_in"))
      (node (ref "U7") (pin "6") (pinfunction "VIN_6") (pintype "power_in"))
      (node (ref "U7") (pin "7") (pinfunction "VINA_7") (pintype "power_in"))
      (node (ref "U7") (pin "8") (pinfunction "EN_8") (pintype "input"))
      (node (ref "U8") (pin "10") (pinfunction "VIN_10") (pintype "input"))
    )
    (net (code "13") (name "/EN_3V3_1") (class "Default")
      (node (ref "R27") (pin "1") (pinfunction "1_1") (pintype "passive"))
      (node (ref "U4") (pin "35") (pinfunction "P1.4/SMCLK/TCK_35") (pintype "bidirectional"))
      (node (ref "U6") (pin "8") (pinfunction "EN_8") (pintype "input"))
    )
    (net (code "14") (name "/EN_3V3_2") (class "Default")
      (node (ref "R104") (pin "1") (pinfunction "1_1") (pintype "passive"))
      (node (ref "U100") (pin "8") (pinfunction "EN_8") (pintype "input"))
      (node (ref "U4") (pin "36") (pinfunction "P1.5/TA0/TMS_36") (pintype "bidirectional"))
    )
    (net (code "15") (name "/EN_3V3_M") (class "Default")
      (node (ref "R24") (pin "1") (pinfunction "1_1") (pintype "passive"))
      (node (ref "U4") (pin "34") (pinfunction "P1.3/TA2_34") (pintype "bidirectional"))
      (node (ref "U5") (pin "4") (pinfunction "EN_4") (pintype "bidirectional"))
    )
    (net (code "16") (name "/EN_5V") (class "Default")
      (node (ref "R30") (pin "2") (pinfunction "2_2") (pintype "passive"))
      (node (ref "U4") (pin "37") (pinfunction "P1.6/TA1/TDI_37") (pintype "bidirectional"))
      (node (ref "U8") (pin "9") (pinfunction "EN_9") (pintype "input"))
    )
    (net (code "17") (name "/EN_12V") (class "Default")
      (node (ref "U$1") (pin "P$2") (pinfunction "EN_P$2") (pintype "bidirectional"))
      (node (ref "U4") (pin "38") (pinfunction "P1.7/TA2/TDO/TDI_38") (pintype "bidirectional"))
    )
    (net (code "18") (name "/EN_HEAT1") (class "Default")
      (node (ref "R3") (pin "2") (pinfunction "2_2") (pintype "passive"))
      (node (ref "R4") (pin "1") (pinfunction "1_1") (pintype "passive"))
      (node (ref "U4") (pin "31") (pinfunction "P1.0/TACLK/ADC10CLK_31") (pintype "bidirectional"))
    )
    (net (code "19") (name "/EN_HEAT2") (class "Default")
      (node (ref "R5") (pin "2") (pinfunction "2_2") (pintype "passive"))
      (node (ref "R6") (pin "1") (pinfunction "1_1") (pintype "passive"))
      (node (ref "U4") (pin "32") (pinfunction "P1.1/TA0_32") (pintype "bidirectional"))
    )
    (net (code "20") (name "/EN_HEAT3") (class "Default")
      (node (ref "R7") (pin "2") (pinfunction "2_2") (pintype "passive"))
      (node (ref "R8") (pin "1") (pinfunction "1_1") (pintype "passive"))
      (node (ref "U4") (pin "33") (pinfunction "P1.2/TA1_33") (pintype "bidirectional"))
    )
    (net (code "21") (name "/EN_SC") (class "Default")
      (node (ref "Q100") (pin "1") (pinfunction "G_1") (pintype "passive"))
      (node (ref "R102") (pin "1") (pinfunction "1_1") (pintype "passive"))
      (node (ref "R103") (pin "2") (pinfunction "2_2") (pintype "passive"))
      (node (ref "U4") (pin "3") (pinfunction "P2.5/ROSC_3") (pintype "bidirectional"))
    )
    (net (code "22") (name "/HEAT1") (class "Default")
      (node (ref "JP4") (pin "12") (pinfunction "12_12") (pintype "passive"))
      (node (ref "U1") (pin "5") (pinfunction "D_2_5") (pintype "passive"))
      (node (ref "U1") (pin "6") (pinfunction "D_3_6") (pintype "passive"))
      (node (ref "U1") (pin "7") (pinfunction "D_4_7") (pintype "passive"))
      (node (ref "U1") (pin "8") (pinfunction "D_8") (pintype "passive"))
    )
    (net (code "23") (name "/HEAT2") (class "Default")
      (node (ref "JP4") (pin "14") (pinfunction "14_14") (pintype "passive"))
      (node (ref "U2") (pin "5") (pinfunction "D_2_5") (pintype "passive"))
      (node (ref "U2") (pin "6") (pinfunction "D_3_6") (pintype "passive"))
      (node (ref "U2") (pin "7") (pinfunction "D_4_7") (pintype "passive"))
      (node (ref "U2") (pin "8") (pinfunction "D_8") (pintype "passive"))
    )
    (net (code "24") (name "/HEAT3") (class "Default")
      (node (ref "JP4") (pin "16") (pinfunction "16_16") (pintype "passive"))
      (node (ref "U3") (pin "5") (pinfunction "D_2_5") (pintype "passive"))
      (node (ref "U3") (pin "6") (pinfunction "D_3_6") (pintype "passive"))
      (node (ref "U3") (pin "7") (pinfunction "D_4_7") (pintype "passive"))
      (node (ref "U3") (pin "8") (pinfunction "D_8") (pintype "passive"))
    )
    (net (code "25") (name "/I2C_SCL") (class "Default")
      (node (ref "JP3") (pin "2") (pinfunction "2_2") (pintype "passive"))
      (node (ref "U4") (pin "13") (pinfunction "P3.2/UCB0SOMI/UCB0SCL_13") (pintype "bidirectional"))
    )
    (net (code "26") (name "/I2C_SDA") (class "Default")
      (node (ref "JP3") (pin "1") (pinfunction "1_1") (pintype "passive"))
      (node (ref "U4") (pin "12") (pinfunction "P3.1/UCB0SIMO/UCB0SDA_12") (pintype "bidirectional"))
    )
    (net (code "27") (name "/I_IN") (class "Default")
      (node (ref "C8") (pin "2") (pinfunction "2_2") (pintype "passive"))
      (node (ref "R25") (pin "1") (pinfunction "1_1") (pintype "passive"))
      (node (ref "U4") (pin "9") (pinfunction "P2.1/TAINCLK/SMCLK/A1_9") (pintype "bidirectional"))
    )
    (net (code "28") (name "/I_OUT") (class "Default")
      (node (ref "C9") (pin "2") (pinfunction "2_2") (pintype "passive"))
      (node (ref "R26") (pin "1") (pinfunction "1_1") (pintype "passive"))
      (node (ref "U4") (pin "8") (pinfunction "P2.0/ACLK/A0_8") (pintype "bidirectional"))
    )
    (net (code "29") (name "/SC+") (class "Default")
      (node (ref "C32") (pin "2") (pinfunction "2_2") (pintype "passive"))
      (node (ref "JP5") (pin "2") (pinfunction "2_2") (pintype "passive"))
      (node (ref "R101") (pin "2") (pinfunction "2_2") (pintype "passive"))
      (node (ref "R102") (pin "2") (pinfunction "2_2") (pintype "passive"))
      (node (ref "R22") (pin "2") (pinfunction "2_2") (pintype "passive"))
      (node (ref "R29") (pin "2") (pinfunction "2_2") (pintype "passive"))
      (node (ref "R31") (pin "2") (pinfunction "2_2") (pintype "passive"))
      (node (ref "R40") (pin "1") (pinfunction "1_1") (pintype "passive"))
      (node (ref "R41") (pin "2") (pinfunction "2_2") (pintype "passive"))
      (node (ref "U10") (pin "5") (pinfunction "D_2_5") (pintype "passive"))
      (node (ref "U10") (pin "6") (pinfunction "D_3_6") (pintype "passive"))
      (node (ref "U10") (pin "7") (pinfunction "D_4_7") (pintype "passive"))
      (node (ref "U10") (pin "8") (pinfunction "D_8") (pintype "passive"))
    )
    (net (code "30") (name "/SC_OUT") (class "Default")
      (node (ref "C26") (pin "1") (pinfunction "1_1") (pintype "passive"))
      (node (ref "C37") (pin "1") (pinfunction "1_1") (pintype "passive"))
      (node (ref "C38") (pin "1") (pinfunction "1_1") (pintype "passive"))
      (node (ref "R32") (pin "2") (pinfunction "2_2") (pintype "passive"))
      (node (ref "R34") (pin "2") (pinfunction "2_2") (pintype "passive"))
      (node (ref "RSENSE1") (pin "I1") (pinfunction "I1_I1") (pintype "bidirectional"))
      (node (ref "R_SENSE1") (pin "I2") (pinfunction "I2_I2") (pintype "bidirectional"))
    )
    (net (code "31") (name "/V_BAT") (class "Default")
      (node (ref "C1") (pin "2") (pinfunction "2_2") (pintype "passive"))
      (node (ref "R1") (pin "1") (pinfunction "1_1") (pintype "passive"))
      (node (ref "U4") (pin "29") (pinfunction "P2.3/TA1/A3/VREF−/VEREF-_29") (pintype "bidirectional"))
    )
    (net (code "32") (name "/V_SC") (class "Default")
      (node (ref "C2") (pin "2") (pinfunction "2_2") (pintype "passive"))
      (node (ref "R2") (pin "1") (pinfunction "1_1") (pintype "passive"))
      (node (ref "U4") (pin "10") (pinfunction "P2.2/TA0/A2_10") (pintype "bidirectional"))
    )
    (net (code "33") (name "GND") (class "Default")
      (node (ref "C1") (pin "1") (pinfunction "1_1") (pintype "passive"))
      (node (ref "C10") (pin "2") (pinfunction "2_2") (pintype "passive"))
      (node (ref "C101") (pin "2") (pinfunction "2_2") (pintype "passive"))
      (node (ref "C102") (pin "2") (pinfunction "2_2") (pintype "passive"))
      (node (ref "C103") (pin "2") (pinfunction "2_2") (pintype "passive"))
      (node (ref "C104") (pin "2") (pinfunction "2_2") (pintype "passive"))
      (node (ref "C11") (pin "2") (pinfunction "2_2") (pintype "passive"))
      (node (ref "C12") (pin "2") (pinfunction "2_2") (pintype "passive"))
      (node (ref "C13") (pin "2") (pinfunction "2_2") (pintype "passive"))
      (node (ref "C14") (pin "2") (pinfunction "2_2") (pintype "passive"))
      (node (ref "C16") (pin "2") (pinfunction "2_2") (pintype "passive"))
      (node (ref "C17") (pin "2") (pinfunction "2_2") (pintype "passive"))
      (node (ref "C18") (pin "2") (pinfunction "2_2") (pintype "passive"))
      (node (ref "C19") (pin "2") (pinfunction "2_2") (pintype "passive"))
      (node (ref "C2") (pin "1") (pinfunction "1_1") (pintype "passive"))
      (node (ref "C20") (pin "2") (pinfunction "2_2") (pintype "passive"))
      (node (ref "C21") (pin "2") (pinfunction "2_2") (pintype "passive"))
      (node (ref "C22") (pin "2") (pinfunction "2_2") (pintype "passive"))
      (node (ref "C23") (pin "2") (pinfunction "2_2") (pintype "passive"))
      (node (ref "C24") (pin "2") (pinfunction "2_2") (pintype "passive"))
      (node (ref "C25") (pin "2") (pinfunction "2_2") (pintype "passive"))
      (node (ref "C27") (pin "1") (pinfunction "1_1") (pintype "passive"))
      (node (ref "C28") (pin "1") (pinfunction "1_1") (pintype "passive"))
      (node (ref "C29") (pin "1") (pinfunction "1_1") (pintype "passive"))
      (node (ref "C3") (pin "2") (pinfunction "2_2") (pintype "passive"))
      (node (ref "C30") (pin "1") (pinfunction "1_1") (pintype "passive"))
      (node (ref "C32") (pin "1") (pinfunction "1_1") (pintype "passive"))
      (node (ref "C33") (pin "2") (pinfunction "2_2") (pintype "passive"))
      (node (ref "C34") (pin "2") (pinfunction "2_2") (pintype "passive"))
      (node (ref "C35") (pin "2") (pinfunction "2_2") (pintype "passive"))
      (node (ref "C36") (pin "2") (pinfunction "2_2") (pintype "passive"))
      (node (ref "C37") (pin "2") (pinfunction "2_2") (pintype "passive"))
      (node (ref "C38") (pin "2") (pinfunction "2_2") (pintype "passive"))
      (node (ref "C4") (pin "2") (pinfunction "2_2") (pintype "passive"))
      (node (ref "C5") (pin "2") (pinfunction "2_2") (pintype "passive"))
      (node (ref "C6") (pin "2") (pinfunction "2_2") (pintype "passive"))
      (node (ref "C7") (pin "-") (pinfunction "-_-") (pintype "passive"))
      (node (ref "C8") (pin "1") (pinfunction "1_1") (pintype "passive"))
      (node (ref "C9") (pin "1") (pinfunction "1_1") (pintype "passive"))
      (node (ref "C_IC1") (pin "1") (pinfunction "1_1") (pintype "passive"))
      (node (ref "IC1") (pin "4") (pinfunction "V-_4") (pintype "power_in"))
      (node (ref "J1") (pin "1") (pinfunction "1_1") (pintype "passive"))
      (node (ref "J2") (pin "1") (pinfunction "1_1") (pintype "passive"))
      (node (ref "J3") (pin "1") (pinfunction "1_1") (pintype "passive"))
      (node (ref "J4") (pin "1") (pinfunction "1_1") (pintype "passive"))
      (node (ref "J5") (pin "1") (pinfunction "1_1") (pintype "passive"))
      (node (ref "J6") (pin "1") (pinfunction "1_1") (pintype "passive"))
      (node (ref "JP1") (pin "2") (pinfunction "2_2") (pintype "passive"))
      (node (ref "JP1") (pin "4") (pinfunction "4_4") (pintype "passive"))
      (node (ref "JP1") (pin "6") (pinfunction "6_6") (pintype "passive"))
      (node (ref "JP1") (pin "8") (pinfunction "8_8") (pintype "passive"))
      (node (ref "JP4") (pin "1") (pinfunction "1_1") (pintype "passive"))
      (node (ref "JP4") (pin "3") (pinfunction "3_3") (pintype "passive"))
      (node (ref "JP4") (pin "5") (pinfunction "5_5") (pintype "passive"))
      (node (ref "JP4") (pin "7") (pinfunction "7_7") (pintype "passive"))
      (node (ref "JP4") (pin "9") (pinfunction "9_9") (pintype "passive"))
      (node (ref "JP5") (pin "1") (pinfunction "1_1") (pintype "passive"))
      (node (ref "JP6") (pin "1") (pinfunction "1_1") (pintype "passive"))
      (node (ref "Q1") (pin "P3") (pinfunction "GND_P3") (pintype "power_in"))
      (node (ref "Q100") (pin "2") (pinfunction "S_2") (pintype "passive"))
      (node (ref "R10") (pin "2") (pinfunction "2_2") (pintype "passive"))
      (node (ref "R100") (pin "1") (pinfunction "1_1") (pintype "passive"))
      (node (ref "R103") (pin "1") (pinfunction "1_1") (pintype "passive"))
      (node (ref "R104") (pin "2") (pinfunction "2_2") (pintype "passive"))
      (node (ref "R18") (pin "2") (pinfunction "2_2") (pintype "passive"))
      (node (ref "R20") (pin "1") (pinfunction "1_1") (pintype "passive"))
      (node (ref "R21") (pin "1") (pinfunction "1_1") (pintype "passive"))
      (node (ref "R27") (pin "2") (pinfunction "2_2") (pintype "passive"))
      (node (ref "R30") (pin "1") (pinfunction "1_1") (pintype "passive"))
      (node (ref "R33") (pin "1") (pinfunction "1_1") (pintype "passive"))
      (node (ref "R35") (pin "1") (pinfunction "1_1") (pintype "passive"))
      (node (ref "R36") (pin "1") (pinfunction "1_1") (pintype "passive"))
      (node (ref "R4") (pin "2") (pinfunction "2_2") (pintype "passive"))
      (node (ref "R6") (pin "2") (pinfunction "2_2") (pintype "passive"))
      (node (ref "R8") (pin "2") (pinfunction "2_2") (pintype "passive"))
      (node (ref "U$1") (pin "P$20") (pinfunction "AGND_P$20") (pintype "bidirectional"))
      (node (ref "U$1") (pin "PGND1") (pinfunction "PGND_PGND1") (pintype "bidirectional"))
      (node (ref "U$1") (pin "PGND10") (pinfunction "PGND_PGND10") (pintype "bidirectional"))
      (node (ref "U$1") (pin "PGND11") (pinfunction "PGND_PGND11") (pintype "bidirectional"))
      (node (ref "U$1") (pin "PGND12") (pinfunction "PGND_PGND12") (pintype "bidirectional"))
      (node (ref "U$1") (pin "PGND2") (pinfunction "PGND_PGND2") (pintype "bidirectional"))
      (node (ref "U$1") (pin "PGND3") (pinfunction "PGND_PGND3") (pintype "bidirectional"))
      (node (ref "U$1") (pin "PGND4") (pinfunction "PGND_PGND4") (pintype "bidirectional"))
      (node (ref "U$1") (pin "PGND5") (pinfunction "PGND_PGND5") (pintype "bidirectional"))
      (node (ref "U$1") (pin "PGND6") (pinfunction "PGND_PGND6") (pintype "bidirectional"))
      (node (ref "U$1") (pin "PGND7") (pinfunction "PGND_PGND7") (pintype "bidirectional"))
      (node (ref "U$1") (pin "PGND8") (pinfunction "PGND_PGND8") (pintype "bidirectional"))
      (node (ref "U$1") (pin "PGND9") (pinfunction "PGND_PGND9") (pintype "bidirectional"))
      (node (ref "U$2") (pin "1") (pinfunction "REF_1") (pintype "bidirectional"))
      (node (ref "U$2") (pin "2") (pinfunction "GND_2") (pintype "bidirectional"))
      (node (ref "U$3") (pin "1") (pinfunction "REF_1") (pintype "bidirectional"))
      (node (ref "U$3") (pin "2") (pinfunction "GND_2") (pintype "bidirectional"))
      (node (ref "U1") (pin "1") (pinfunction "S_2_1") (pintype "passive"))
      (node (ref "U1") (pin "2") (pinfunction "S_3_2") (pintype "passive"))
      (node (ref "U1") (pin "3") (pinfunction "S_3") (pintype "passive"))
      (node (ref "U100") (pin "10") (pinfunction "PFM_PWM_10") (pintype "input"))
      (node (ref "U100") (pin "2") (pinfunction "PGND_2") (pintype "power_in"))
      (node (ref "U100") (pin "9") (pinfunction "GND_9") (pintype "power_in"))
      (node (ref "U11") (pin "1") (pinfunction "S_2_1") (pintype "passive"))
      (node (ref "U11") (pin "2") (pinfunction "S_3_2") (pintype "passive"))
      (node (ref "U11") (pin "3") (pinfunction "S_3") (pintype "passive"))
      (node (ref "U2") (pin "1") (pinfunction "S_2_1") (pintype "passive"))
      (node (ref "U2") (pin "2") (pinfunction "S_3_2") (pintype "passive"))
      (node (ref "U2") (pin "3") (pinfunction "S_3") (pintype "passive"))
      (node (ref "U3") (pin "1") (pinfunction "S_2_1") (pintype "passive"))
      (node (ref "U3") (pin "2") (pinfunction "S_3_2") (pintype "passive"))
      (node (ref "U3") (pin "3") (pinfunction "S_3") (pintype "passive"))
      (node (ref "U4") (pin "15") (pinfunction "AVSS_15") (pintype "bidirectional"))
      (node (ref "U4") (pin "4") (pinfunction "DVSS_4") (pintype "bidirectional"))
      (node (ref "U5") (pin "1") (pinfunction "GND_1") (pintype "bidirectional"))
      (node (ref "U6") (pin "10") (pinfunction "PFM_PWM_10") (pintype "input"))
      (node (ref "U6") (pin "2") (pinfunction "PGND_2") (pintype "power_in"))
      (node (ref "U6") (pin "9") (pinfunction "GND_9") (pintype "power_in"))
      (node (ref "U7") (pin "10") (pinfunction "PFM_PWM_10") (pintype "input"))
      (node (ref "U7") (pin "2") (pinfunction "PGND_2") (pintype "power_in"))
      (node (ref "U7") (pin "9") (pinfunction "GND_9") (pintype "power_in"))
      (node (ref "U8") (pin "EXPAD") (pinfunction "GND_EXPAD") (pintype "power_in"))
      (node (ref "U8") (pin "GND1") (pinfunction "GND1_GND1") (pintype "power_in"))
      (node (ref "U8") (pin "GND2") (pinfunction "GND2_GND2") (pintype "power_in"))
      (node (ref "U8") (pin "GND3") (pinfunction "GND3_GND3") (pintype "power_in"))
      (node (ref "U8") (pin "GND4") (pinfunction "GND4_GND4") (pintype "power_in"))
      (node (ref "U8") (pin "GND5") (pinfunction "GND5_GND5") (pintype "power_in"))
      (node (ref "U9") (pin "11") (pinfunction "GND_11") (pintype "power_in"))
      (node (ref "U9") (pin "17") (pinfunction "EPAD_17") (pintype "power_in"))
      (node (ref "U9") (pin "7") (pinfunction "TERM_EN_7") (pintype "input"))
      (node (ref "U9") (pin "V") (pinfunction "EPAD_V") (pintype "power_in"))
      (node (ref "U9") (pin "V_1") (pinfunction "EPAD_V_1") (pintype "power_in"))
      (node (ref "U9") (pin "V_2") (pinfunction "EPAD_V_2") (pintype "power_in"))
      (node (ref "U9") (pin "V_3") (pinfunction "EPAD_V_3") (pintype "power_in"))
    )
    (net (code "34") (name "Net-(+3V3_1-PadC)") (class "Default")
      (node (ref "+3V3_1") (pin "C") (pinfunction "C_C") (pintype "passive"))
      (node (ref "R13") (pin "2") (pinfunction "2_2") (pintype "passive"))
    )
    (net (code "35") (name "Net-(+3V3_2-PadC)") (class "Default")
      (node (ref "+3V3_2") (pin "C") (pinfunction "C_C") (pintype "passive"))
      (node (ref "R14") (pin "2") (pinfunction "2_2") (pintype "passive"))
    )
    (net (code "36") (name "Net-(+3V3_M-PadC)") (class "Default")
      (node (ref "+3V3_M") (pin "C") (pinfunction "C_C") (pintype "passive"))
      (node (ref "R12") (pin "2") (pinfunction "2_2") (pintype "passive"))
    )
    (net (code "37") (name "Net-(+5V-PadC)") (class "Default")
      (node (ref "+5V") (pin "C") (pinfunction "C_C") (pintype "passive"))
      (node (ref "R15") (pin "2") (pinfunction "2_2") (pintype "passive"))
    )
    (net (code "38") (name "Net-(+11V-PadC)") (class "Default")
      (node (ref "+11V") (pin "C") (pinfunction "C_C") (pintype "passive"))
      (node (ref "R16") (pin "2") (pinfunction "2_2") (pintype "passive"))
    )
    (net (code "39") (name "Net-(6.8UH-Pad2)") (class "Default")
      (node (ref "6.8UH") (pin "2") (pinfunction "2_2") (pintype "passive"))
      (node (ref "R_SENSE1") (pin "I1") (pinfunction "I1_I1") (pintype "bidirectional"))
    )
    (net (code "40") (name "Net-(C22-Pad1)") (class "Default")
      (node (ref "C22") (pin "1") (pinfunction "1_1") (pintype "passive"))
      (node (ref "R41") (pin "1") (pinfunction "1_1") (pintype "passive"))
    )
    (net (code "41") (name "Net-(C25-Pad1)") (class "Default")
      (node (ref "C25") (pin "1") (pinfunction "1_1") (pintype "passive"))
      (node (ref "R37") (pin "1") (pinfunction "1_1") (pintype "passive"))
    )
    (net (code "42") (name "Net-(D1-A1)") (class "Default")
      (node (ref "C101") (pin "1") (pinfunction "1_1") (pintype "passive"))
      (node (ref "D1") (pin "1") (pinfunction "A1_1") (pintype "passive"))
      (node (ref "D1") (pin "2") (pinfunction "A2_2") (pintype "passive"))
      (node (ref "U9") (pin "12") (pinfunction "REGN_12") (pintype "power_in"))
    )
    (net (code "43") (name "Net-(D1-CC)") (class "Default")
      (node (ref "C100") (pin "2") (pinfunction "2_2") (pintype "passive"))
      (node (ref "D1") (pin "3") (pinfunction "CC_3") (pintype "passive"))
      (node (ref "U9") (pin "16") (pinfunction "BTST_16") (pintype "power_in"))
    )
    (net (code "44") (name "Net-(IC1A-+IN)") (class "Default")
      (node (ref "IC1") (pin "3") (pinfunction "+IN_3") (pintype "input"))
      (node (ref "R21") (pin "2") (pinfunction "2_2") (pintype "passive"))
      (node (ref "R23") (pin "1") (pinfunction "1_1") (pintype "passive"))
    )
    (net (code "45") (name "Net-(IC1A--IN)") (class "Default")
      (node (ref "IC1") (pin "2") (pinfunction "-IN_2") (pintype "input"))
      (node (ref "R10") (pin "1") (pinfunction "1_1") (pintype "passive"))
      (node (ref "R9") (pin "2") (pinfunction "2_2") (pintype "passive"))
    )
    (net (code "46") (name "Net-(IC1A-OUT)") (class "Default")
      (node (ref "IC1") (pin "1") (pinfunction "OUT_1") (pintype "output"))
      (node (ref "R1") (pin "2") (pinfunction "2_2") (pintype "passive"))
      (node (ref "R9") (pin "1") (pinfunction "1_1") (pintype "passive"))
    )
    (net (code "47") (name "Net-(IC1B-+IN)") (class "Default")
      (node (ref "IC1") (pin "5") (pinfunction "+IN_5") (pintype "input"))
      (node (ref "R20") (pin "2") (pinfunction "2_2") (pintype "passive"))
      (node (ref "R22") (pin "1") (pinfunction "1_1") (pintype "passive"))
    )
    (net (code "48") (name "Net-(IC1B--IN)") (class "Default")
      (node (ref "IC1") (pin "6") (pinfunction "-IN_6") (pintype "input"))
      (node (ref "R17") (pin "2") (pinfunction "2_2") (pintype "passive"))
      (node (ref "R18") (pin "1") (pinfunction "1_1") (pintype "passive"))
    )
    (net (code "49") (name "Net-(IC1B-OUT)") (class "Default")
      (node (ref "IC1") (pin "7") (pinfunction "OUT_7") (pintype "output"))
      (node (ref "R17") (pin "1") (pinfunction "1_1") (pintype "passive"))
      (node (ref "R2") (pin "2") (pinfunction "2_2") (pintype "passive"))
    )
    (net (code "50") (name "Net-(J1-Pad2)") (class "Default")
      (node (ref "J1") (pin "2") (pinfunction "2_2") (pintype "passive"))
      (node (ref "R11") (pin "1") (pinfunction "1_1") (pintype "passive"))
    )
    (net (code "51") (name "Net-(J2-Pad2)") (class "Default")
      (node (ref "J2") (pin "2") (pinfunction "2_2") (pintype "passive"))
      (node (ref "R12") (pin "1") (pinfunction "1_1") (pintype "passive"))
    )
    (net (code "52") (name "Net-(J3-Pad2)") (class "Default")
      (node (ref "J3") (pin "2") (pinfunction "2_2") (pintype "passive"))
      (node (ref "R13") (pin "1") (pinfunction "1_1") (pintype "passive"))
    )
    (net (code "53") (name "Net-(J4-Pad2)") (class "Default")
      (node (ref "J4") (pin "2") (pinfunction "2_2") (pintype "passive"))
      (node (ref "R14") (pin "1") (pinfunction "1_1") (pintype "passive"))
    )
    (net (code "54") (name "Net-(J5-Pad2)") (class "Default")
      (node (ref "J5") (pin "2") (pinfunction "2_2") (pintype "passive"))
      (node (ref "R15") (pin "1") (pinfunction "1_1") (pintype "passive"))
    )
    (net (code "55") (name "Net-(J6-Pad2)") (class "Default")
      (node (ref "J6") (pin "2") (pinfunction "2_2") (pintype "passive"))
      (node (ref "R16") (pin "1") (pinfunction "1_1") (pintype "passive"))
    )
    (net (code "56") (name "Net-(J7-Pad2)") (class "Default")
      (node (ref "J7") (pin "2") (pinfunction "2_2") (pintype "passive"))
      (node (ref "STAT2") (pin "C") (pinfunction "C_C") (pintype "passive"))
    )
    (net (code "57") (name "Net-(J8-Pad2)") (class "Default")
      (node (ref "J8") (pin "2") (pinfunction "2_2") (pintype "passive"))
      (node (ref "STAT1") (pin "C") (pinfunction "C_C") (pintype "passive"))
    )
    (net (code "58") (name "Net-(L1-1)") (class "Default")
      (node (ref "L1") (pin "P$1") (pinfunction "1_P$1") (pintype "passive"))
      (node (ref "U6") (pin "3") (pinfunction "L1_3") (pintype "passive"))
    )
    (net (code "59") (name "Net-(L1-2)") (class "Default")
      (node (ref "L1") (pin "P$2") (pinfunction "2_P$2") (pintype "passive"))
      (node (ref "U6") (pin "1") (pinfunction "L2_1") (pintype "passive"))
    )
    (net (code "60") (name "Net-(L2-1)") (class "Default")
      (node (ref "L2") (pin "P$1") (pinfunction "1_P$1") (pintype "passive"))
      (node (ref "U7") (pin "3") (pinfunction "L1_3") (pintype "passive"))
    )
    (net (code "61") (name "Net-(L2-2)") (class "Default")
      (node (ref "L2") (pin "P$2") (pinfunction "2_P$2") (pintype "passive"))
      (node (ref "U7") (pin "1") (pinfunction "L2_1") (pintype "passive"))
    )
    (net (code "62") (name "Net-(L3-2)") (class "Default")
      (node (ref "L3") (pin "P$2") (pinfunction "2_P$2") (pintype "passive"))
      (node (ref "U8") (pin "1") (pinfunction "SW_1") (pintype "power_in"))
      (node (ref "U8") (pin "2") (pinfunction "SW_2") (pintype "power_in"))
    )
    (net (code "63") (name "Net-(L4-2)") (class "Default")
      (node (ref "C31") (pin "1") (pinfunction "1_1") (pintype "passive"))
      (node (ref "L4") (pin "P$2") (pinfunction "2_P$2") (pintype "passive"))
      (node (ref "R39") (pin "2") (pinfunction "2_2") (pintype "passive"))
      (node (ref "U$1") (pin "P$4") (pinfunction "SW1_P$4") (pintype "bidirectional"))
      (node (ref "U$1") (pin "P$5") (pinfunction "SW2_P$5") (pintype "bidirectional"))
      (node (ref "U$1") (pin "P$6") (pinfunction "SW3_P$6") (pintype "bidirectional"))
      (node (ref "U$1") (pin "P$7") (pinfunction "SW4_P$7") (pintype "bidirectional"))
    )
    (net (code "64") (name "Net-(L100-1)") (class "Default")
      (node (ref "L100") (pin "P$1") (pinfunction "1_P$1") (pintype "passive"))
      (node (ref "U100") (pin "3") (pinfunction "L1_3") (pintype "passive"))
    )
    (net (code "65") (name "Net-(L100-2)") (class "Default")
      (node (ref "L100") (pin "P$2") (pinfunction "2_P$2") (pintype "passive"))
      (node (ref "U100") (pin "1") (pinfunction "L2_1") (pintype "passive"))
    )
    (net (code "66") (name "Net-(Q1-1)") (class "Default")
      (node (ref "Q1") (pin "P1") (pinfunction "1_P1") (pintype "bidirectional"))
      (node (ref "U4") (pin "6") (pinfunction "XIN/P2.6_6") (pintype "bidirectional"))
    )
    (net (code "67") (name "Net-(Q1-2)") (class "Default")
      (node (ref "Q1") (pin "P2") (pinfunction "2_P2") (pintype "bidirectional"))
      (node (ref "U4") (pin "5") (pinfunction "XOUT/P2.7_5") (pintype "bidirectional"))
    )
    (net (code "68") (name "Net-(Q100-D)") (class "Default")
      (node (ref "Q100") (pin "3") (pinfunction "D_3") (pintype "passive"))
      (node (ref "R100") (pin "2") (pinfunction "2_2") (pintype "passive"))
      (node (ref "R101") (pin "1") (pinfunction "1_1") (pintype "passive"))
      (node (ref "U9") (pin "2") (pinfunction "MPPSET_2") (pintype "input"))
    )
    (net (code "69") (name "Net-(R11-Pad2)") (class "Default")
      (node (ref "R11") (pin "2") (pinfunction "2_2") (pintype "passive"))
      (node (ref "VCC") (pin "C") (pinfunction "C_C") (pintype "passive"))
    )
    (net (code "70") (name "Net-(R29-Pad1)") (class "Default")
      (node (ref "R29") (pin "1") (pinfunction "1_1") (pintype "passive"))
      (node (ref "STAT2") (pin "A") (pinfunction "A_A") (pintype "passive"))
    )
    (net (code "71") (name "Net-(R31-Pad1)") (class "Default")
      (node (ref "R31") (pin "1") (pinfunction "1_1") (pintype "passive"))
      (node (ref "STAT1") (pin "A") (pinfunction "A_A") (pintype "passive"))
    )
    (net (code "72") (name "Net-(U$1-BOOT)") (class "Default")
      (node (ref "C31") (pin "2") (pinfunction "2_2") (pintype "passive"))
      (node (ref "U$1") (pin "P$8") (pinfunction "BOOT_P$8") (pintype "bidirectional"))
    )
    (net (code "73") (name "Net-(U$1-COMP)") (class "Default")
      (node (ref "C24") (pin "1") (pinfunction "1_1") (pintype "passive"))
      (node (ref "R37") (pin "2") (pinfunction "2_2") (pintype "passive"))
      (node (ref "U$1") (pin "P$18") (pinfunction "COMP_P$18") (pintype "bidirectional"))
    )
    (net (code "74") (name "Net-(U$1-FB)") (class "Default")
      (node (ref "R36") (pin "2") (pinfunction "2_2") (pintype "passive"))
      (node (ref "R38") (pin "1") (pinfunction "1_1") (pintype "passive"))
      (node (ref "U$1") (pin "P$17") (pinfunction "FB_P$17") (pintype "bidirectional"))
    )
    (net (code "75") (name "Net-(U$1-FSW)") (class "Default")
      (node (ref "R39") (pin "1") (pinfunction "1_1") (pintype "passive"))
      (node (ref "U$1") (pin "P$3") (pinfunction "FSW_P$3") (pintype "bidirectional"))
    )
    (net (code "76") (name "Net-(U$1-ILIM)") (class "Default")
      (node (ref "R35") (pin "2") (pinfunction "2_2") (pintype "passive"))
      (node (ref "U$1") (pin "P$19") (pinfunction "ILIM_P$19") (pintype "bidirectional"))
    )
    (net (code "77") (name "Net-(U$1-SS)") (class "Default")
      (node (ref "C36") (pin "1") (pinfunction "1_1") (pintype "passive"))
      (node (ref "U$1") (pin "P$10") (pinfunction "SS_P$10") (pintype "bidirectional"))
    )
    (net (code "78") (name "Net-(U$1-VCC)") (class "Default")
      (node (ref "C23") (pin "1") (pinfunction "1_1") (pintype "passive"))
      (node (ref "U$1") (pin "P$1") (pinfunction "VCC_P$1") (pintype "bidirectional"))
    )
    (net (code "79") (name "Net-(U$2-IN+)") (class "Default")
      (node (ref "RSENSE1") (pin "V1") (pinfunction "V1_V1") (pintype "bidirectional"))
      (node (ref "U$2") (pin "4") (pinfunction "IN+_4") (pintype "bidirectional"))
    )
    (net (code "80") (name "Net-(U$2-IN-)") (class "Default")
      (node (ref "RSENSE1") (pin "V2") (pinfunction "V2_V2") (pintype "bidirectional"))
      (node (ref "U$2") (pin "5") (pinfunction "IN-_5") (pintype "bidirectional"))
    )
    (net (code "81") (name "Net-(U$2-OUT)") (class "Default")
      (node (ref "R25") (pin "2") (pinfunction "2_2") (pintype "passive"))
      (node (ref "U$2") (pin "6") (pinfunction "OUT_6") (pintype "bidirectional"))
    )
    (net (code "82") (name "Net-(U$3-IN+)") (class "Default")
      (node (ref "R_SENSE2") (pin "V1") (pinfunction "V1_V1") (pintype "bidirectional"))
      (node (ref "U$3") (pin "4") (pinfunction "IN+_4") (pintype "bidirectional"))
    )
    (net (code "83") (name "Net-(U$3-IN-)") (class "Default")
      (node (ref "R_SENSE2") (pin "V2") (pinfunction "V2_V2") (pintype "bidirectional"))
      (node (ref "U$3") (pin "5") (pinfunction "IN-_5") (pintype "bidirectional"))
    )
    (net (code "84") (name "Net-(U$3-OUT)") (class "Default")
      (node (ref "R26") (pin "2") (pinfunction "2_2") (pintype "passive"))
      (node (ref "U$3") (pin "6") (pinfunction "OUT_6") (pintype "bidirectional"))
    )
    (net (code "85") (name "Net-(U1-G)") (class "Default")
      (node (ref "R3") (pin "1") (pinfunction "1_1") (pintype "passive"))
      (node (ref "U1") (pin "4") (pinfunction "G_4") (pintype "passive"))
    )
    (net (code "86") (name "Net-(U2-G)") (class "Default")
      (node (ref "R5") (pin "1") (pinfunction "1_1") (pintype "passive"))
      (node (ref "U2") (pin "4") (pinfunction "G_4") (pintype "passive"))
    )
    (net (code "87") (name "Net-(U3-G)") (class "Default")
      (node (ref "R7") (pin "1") (pinfunction "1_1") (pintype "passive"))
      (node (ref "U3") (pin "4") (pinfunction "G_4") (pintype "passive"))
    )
    (net (code "88") (name "Net-(U4-AVCC)") (class "Default")
      (node (ref "C3") (pin "1") (pinfunction "1_1") (pintype "passive"))
      (node (ref "FERRITE") (pin "2") (pinfunction "2_2") (pintype "passive"))
      (node (ref "U4") (pin "16") (pinfunction "AVCC_16") (pintype "bidirectional"))
    )
    (net (code "89") (name "Net-(U4-RST{slash}NMI{slash}SBWTDIO)") (class "Default")
      (node (ref "JP2") (pin "1") (pinfunction "1_1") (pintype "passive"))
      (node (ref "R19") (pin "1") (pinfunction "1_1") (pintype "passive"))
      (node (ref "U4") (pin "7") (pinfunction "RST/NMI/SBWTDIO_7") (pintype "bidirectional"))
    )
    (net (code "90") (name "Net-(U4-TEST{slash}SBWTCK)") (class "Default")
      (node (ref "JP2") (pin "2") (pinfunction "2_2") (pintype "passive"))
      (node (ref "U4") (pin "1") (pinfunction "TEST/SBWTCK_1") (pintype "bidirectional"))
    )
    (net (code "91") (name "Net-(U8-PG)") (class "Default")
      (node (ref "R28") (pin "1") (pinfunction "1_1") (pintype "passive"))
      (node (ref "U8") (pin "5") (pinfunction "PG_5") (pintype "output"))
    )
    (net (code "92") (name "Net-(U8-SS)") (class "Default")
      (node (ref "C13") (pin "1") (pinfunction "1_1") (pintype "passive"))
      (node (ref "U8") (pin "6") (pinfunction "SS_6") (pintype "bidirectional"))
    )
    (net (code "93") (name "Net-(U9-SRN)") (class "Default")
      (node (ref "C15") (pin "1") (pinfunction "1_1") (pintype "passive"))
      (node (ref "R_SENSE1") (pin "V2") (pinfunction "V2_V2") (pintype "bidirectional"))
      (node (ref "U9") (pin "9") (pinfunction "SRN_9") (pintype "input"))
    )
    (net (code "94") (name "Net-(U9-SRP)") (class "Default")
      (node (ref "C15") (pin "2") (pinfunction "2_2") (pintype "passive"))
      (node (ref "R_SENSE1") (pin "V1") (pinfunction "V1_V1") (pintype "bidirectional"))
      (node (ref "U9") (pin "10") (pinfunction "SRP_10") (pintype "bidirectional"))
    )
    (net (code "95") (name "Net-(U9-STAT1)") (class "Default")
      (node (ref "J8") (pin "1") (pinfunction "1_1") (pintype "passive"))
      (node (ref "U9") (pin "3") (pinfunction "STAT1_3") (pintype "output"))
    )
    (net (code "96") (name "Net-(U9-STAT2)") (class "Default")
      (node (ref "J7") (pin "1") (pinfunction "1_1") (pintype "passive"))
      (node (ref "U9") (pin "5") (pinfunction "STAT2_5") (pintype "output"))
    )
    (net (code "97") (name "Net-(U9-VCC)") (class "Default")
      (node (ref "C21") (pin "1") (pinfunction "1_1") (pintype "passive"))
      (node (ref "R40") (pin "2") (pinfunction "2_2") (pintype "passive"))
      (node (ref "U9") (pin "1") (pinfunction "VCC_1") (pintype "power_in"))
    )
    (net (code "98") (name "Net-(U9-VFB)") (class "Default")
      (node (ref "C26") (pin "2") (pinfunction "2_2") (pintype "passive"))
      (node (ref "R32") (pin "1") (pinfunction "1_1") (pintype "passive"))
      (node (ref "R33") (pin "2") (pinfunction "2_2") (pintype "passive"))
      (node (ref "R34") (pin "1") (pinfunction "1_1") (pintype "passive"))
      (node (ref "U9") (pin "8") (pinfunction "VFB_8") (pintype "input"))
    )
    (net (code "99") (name "Net-(U9-VREF)") (class "Default")
      (node (ref "C20") (pin "1") (pinfunction "1_1") (pintype "passive"))
      (node (ref "U9") (pin "6") (pinfunction "VREF_6") (pintype "power_in"))
    )
    (net (code "100") (name "Net-(U10-G)") (class "Default")
      (node (ref "U10") (pin "4") (pinfunction "G_4") (pintype "passive"))
      (node (ref "U9") (pin "15") (pinfunction "HIDRV_15") (pintype "output"))
    )
    (net (code "101") (name "Net-(U10-S)") (class "Default")
      (node (ref "6.8UH") (pin "1") (pinfunction "1_1") (pintype "passive"))
      (node (ref "C100") (pin "1") (pinfunction "1_1") (pintype "passive"))
      (node (ref "U10") (pin "1") (pinfunction "S_2_1") (pintype "passive"))
      (node (ref "U10") (pin "2") (pinfunction "S_3_2") (pintype "passive"))
      (node (ref "U10") (pin "3") (pinfunction "S_3") (pintype "passive"))
      (node (ref "U11") (pin "5") (pinfunction "D_2_5") (pintype "passive"))
      (node (ref "U11") (pin "6") (pinfunction "D_3_6") (pintype "passive"))
      (node (ref "U11") (pin "7") (pinfunction "D_4_7") (pintype "passive"))
      (node (ref "U11") (pin "8") (pinfunction "D_8") (pintype "passive"))
      (node (ref "U9") (pin "14") (pinfunction "PH_14") (pintype "power_in"))
    )
    (net (code "102") (name "Net-(U11-G)") (class "Default")
      (node (ref "U11") (pin "4") (pinfunction "G_4") (pintype "passive"))
      (node (ref "U9") (pin "13") (pinfunction "LODRV_13") (pintype "output"))
    )
    (net (code "103") (name "unconnected-(U$1-MODE-PadP$13)") (class "Default")
      (node (ref "U$1") (pin "P$13") (pinfunction "MODE_P$13") (pintype "bidirectional"))
    )
    (net (code "104") (name "unconnected-(U4-P3.3{slash}UCB0CLK{slash}UCA0STE-Pad14)") (class "Default")
      (node (ref "U4") (pin "14") (pinfunction "P3.3/UCB0CLK/UCA0STE_14") (pintype "bidirectional"))
    )
    (net (code "105") (name "unconnected-(U4-P3.4{slash}UCA0TXD{slash}UCA0SIMO-Pad25)") (class "Default")
      (node (ref "U4") (pin "25") (pinfunction "P3.4/UCA0TXD/UCA0SIMO_25") (pintype "bidirectional"))
    )
    (net (code "106") (name "unconnected-(U4-P3.5{slash}UCA0RXD{slash}UCA0SOMI-Pad26)") (class "Default")
      (node (ref "U4") (pin "26") (pinfunction "P3.5/UCA0RXD/UCA0SOMI_26") (pintype "bidirectional"))
    )
    (net (code "107") (name "unconnected-(U4-P4.0{slash}TB0-Pad17)") (class "Default")
      (node (ref "U4") (pin "17") (pinfunction "P4.0/TB0_17") (pintype "bidirectional"))
    )
    (net (code "108") (name "unconnected-(U4-P4.1{slash}TB1-Pad18)") (class "Default")
      (node (ref "U4") (pin "18") (pinfunction "P4.1/TB1_18") (pintype "bidirectional"))
    )
    (net (code "109") (name "unconnected-(U4-P4.2{slash}TB2-Pad19)") (class "Default")
      (node (ref "U4") (pin "19") (pinfunction "P4.2/TB2_19") (pintype "bidirectional"))
    )
    (net (code "110") (name "unconnected-(U4-P4.3{slash}TB0{slash}A12-Pad20)") (class "Default")
      (node (ref "U4") (pin "20") (pinfunction "P4.3/TB0/A12_20") (pintype "bidirectional"))
    )
    (net (code "111") (name "unconnected-(U4-P4.4{slash}TB1{slash}A13-Pad21)") (class "Default")
      (node (ref "U4") (pin "21") (pinfunction "P4.4/TB1/A13_21") (pintype "bidirectional"))
    )
    (net (code "112") (name "unconnected-(U4-P4.5{slash}TB2{slash}A14-Pad22)") (class "Default")
      (node (ref "U4") (pin "22") (pinfunction "P4.5/TB2/A14_22") (pintype "bidirectional"))
    )
    (net (code "113") (name "unconnected-(U4-P4.6{slash}TBOUTH{slash}A15-Pad23)") (class "Default")
      (node (ref "U4") (pin "23") (pinfunction "P4.6/TBOUTH/A15_23") (pintype "bidirectional"))
    )
    (net (code "114") (name "unconnected-(U4-P4.7{slash}TBCLK-Pad24)") (class "Default")
      (node (ref "U4") (pin "24") (pinfunction "P4.7/TBCLK_24") (pintype "bidirectional"))
    )
    (net (code "115") (name "unconnected-(U5-OC-Pad5)") (class "Default")
      (node (ref "U5") (pin "5") (pinfunction "OC_5") (pintype "bidirectional"))
    )
    (net (code "116") (name "unconnected-(U8-HYS-Pad8)") (class "Default")
      (node (ref "U8") (pin "8") (pinfunction "HYS_8") (pintype "output"))
    )
    (net (code "117") (name "unconnected-(U9-TS-Pad4)") (class "Default")
      (node (ref "U9") (pin "4") (pinfunction "TS_4") (pintype "input"))
    )
  )
)
